# ab_v11_panel.net
KiCad netlist of a schematic drawn in EAGLE
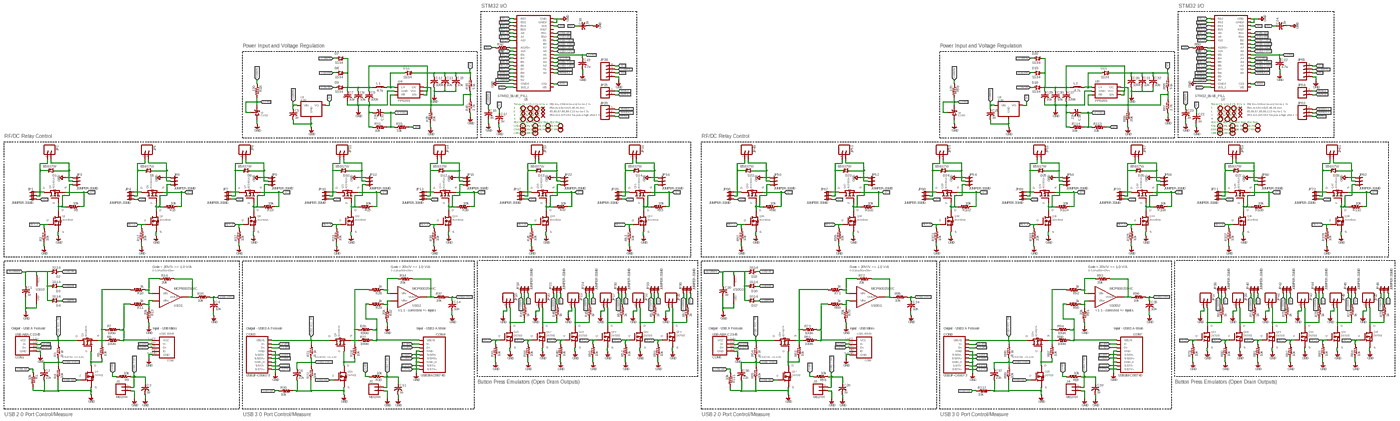
[diagram p0: schematic, sheet 1, overview]
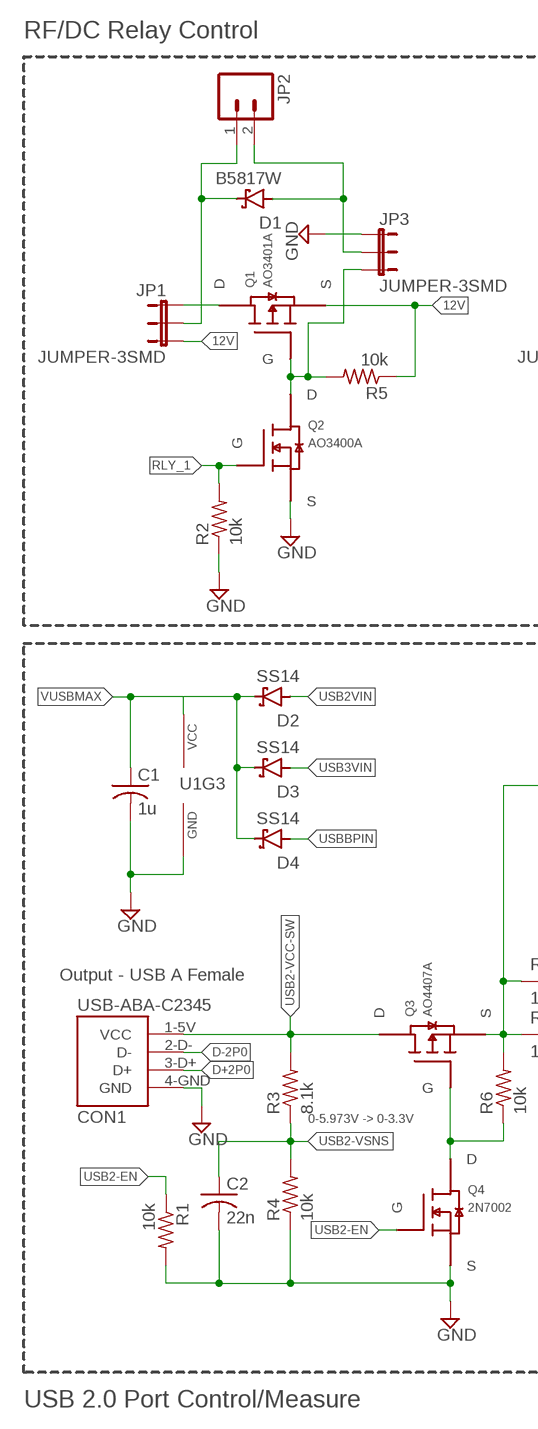
[diagram p1: schematic, sheet 1, part 1 of 4]
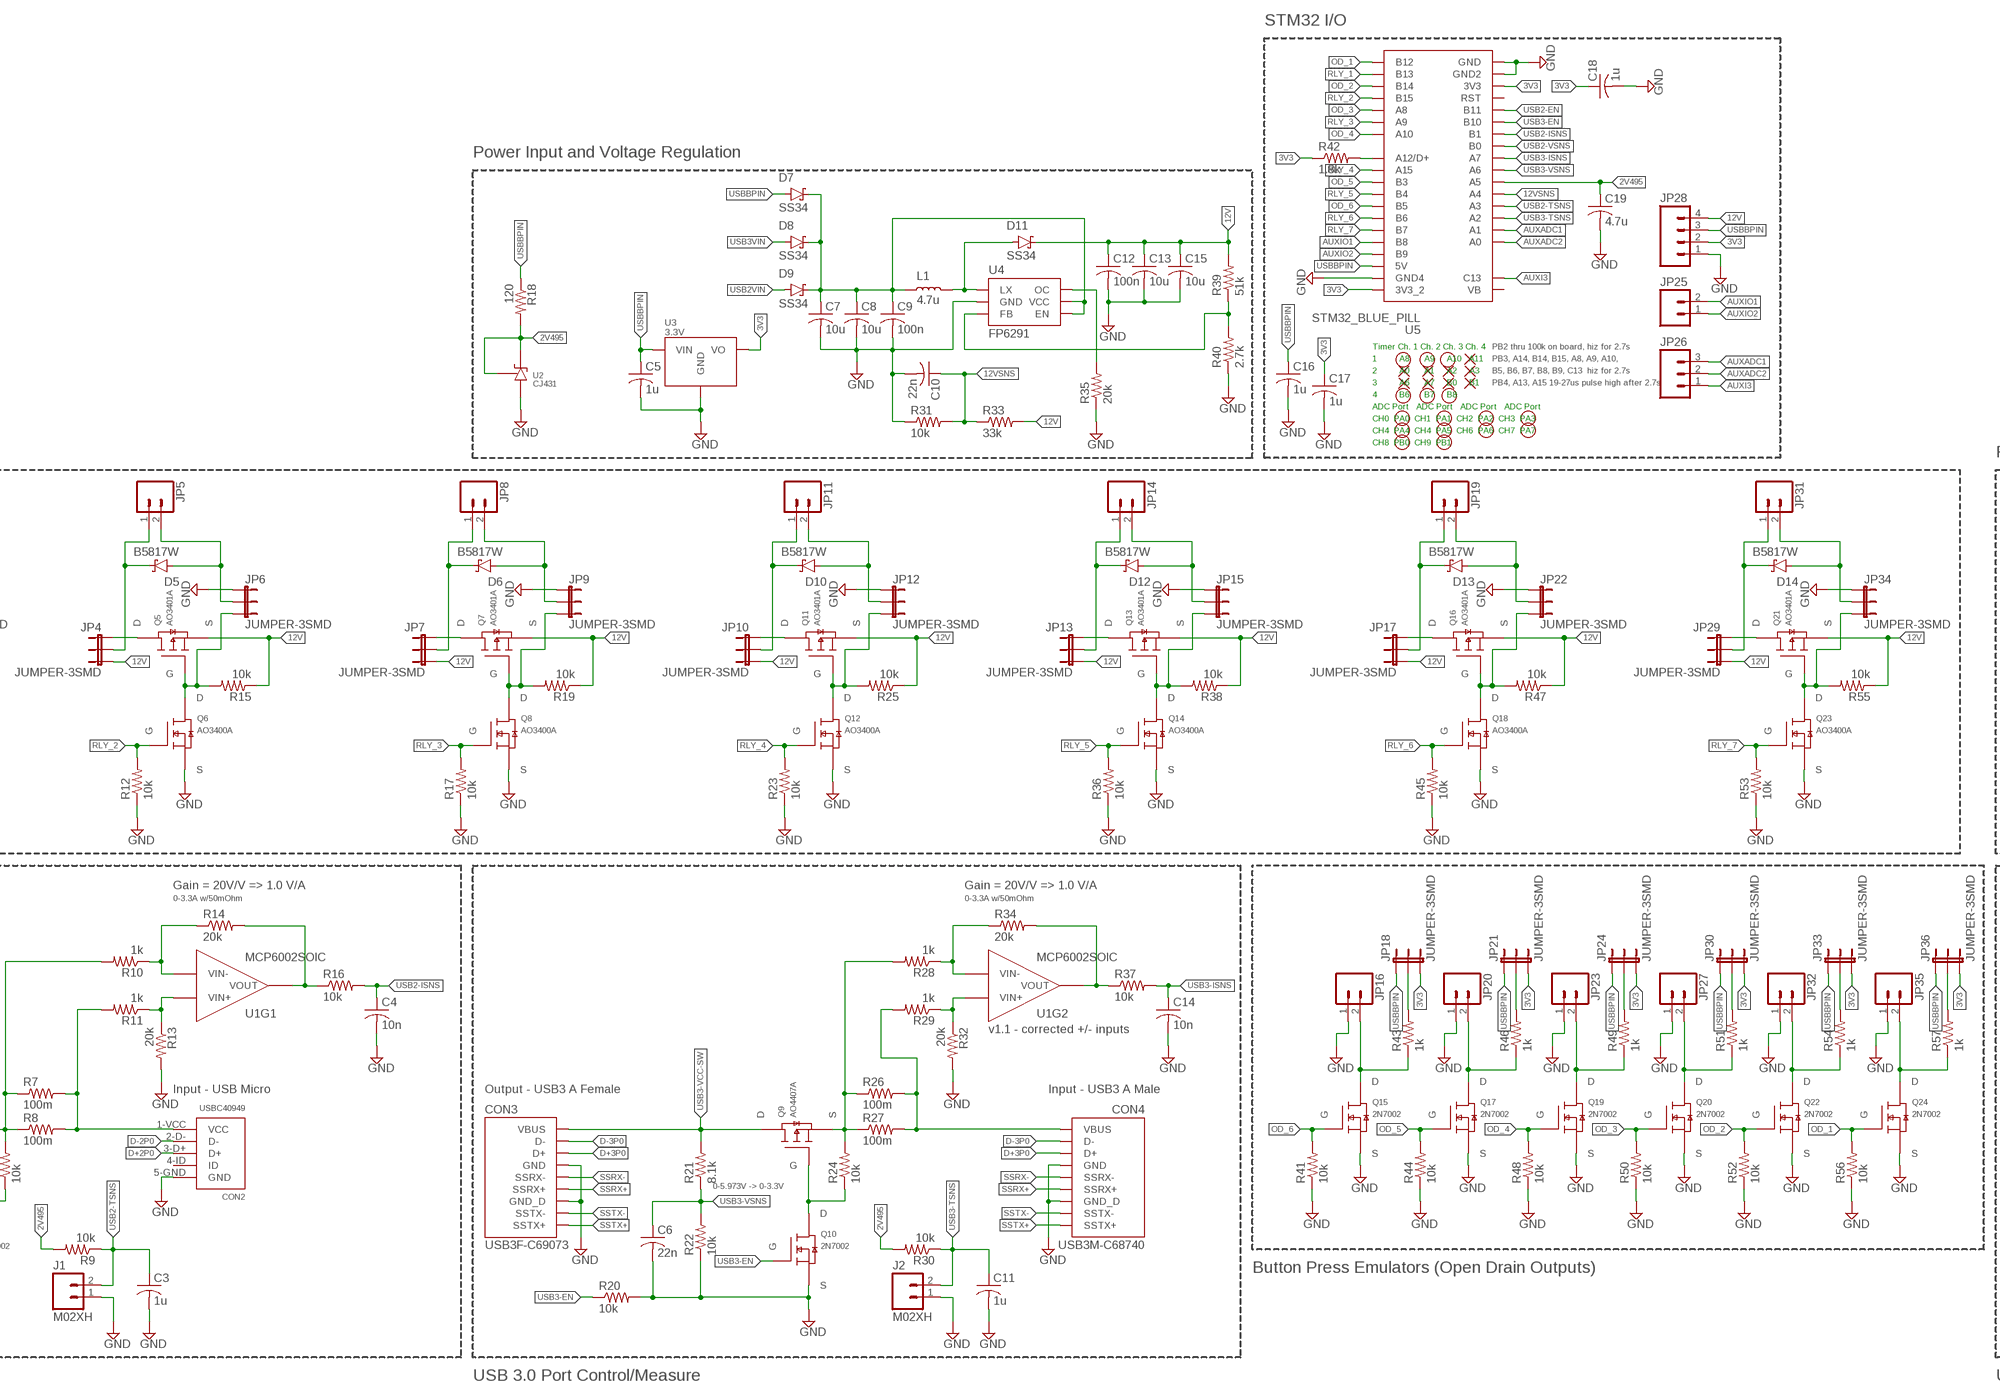
[diagram p2: schematic, sheet 1, part 2 of 4]
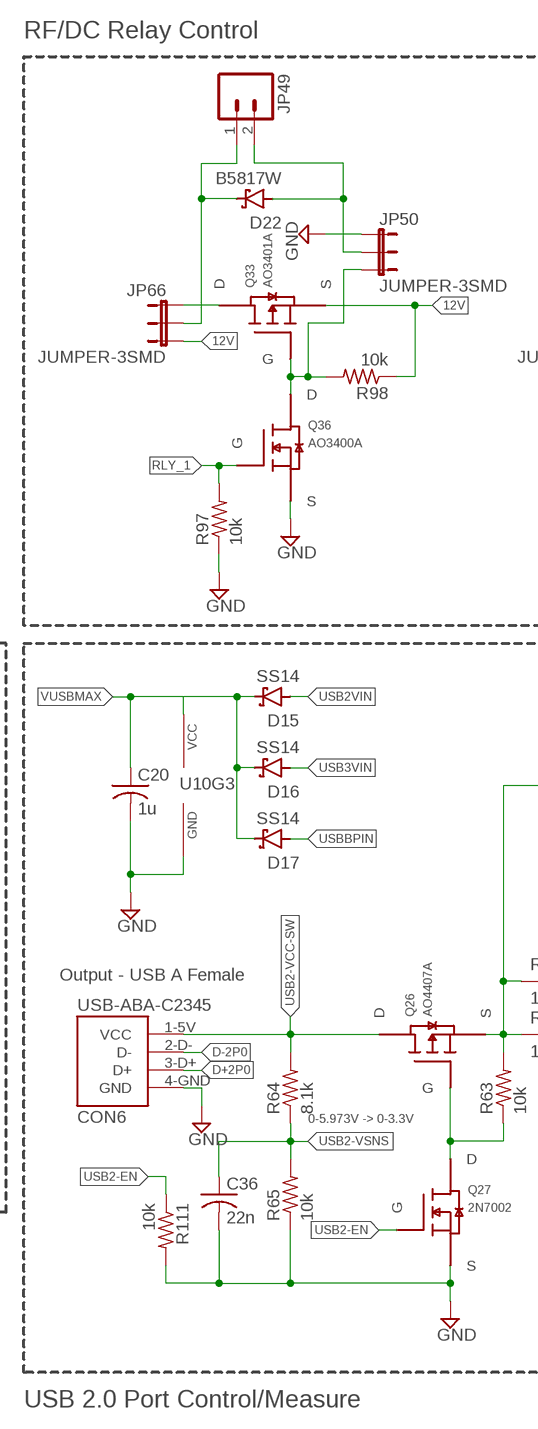
[diagram p3: schematic, sheet 1, part 3 of 4]
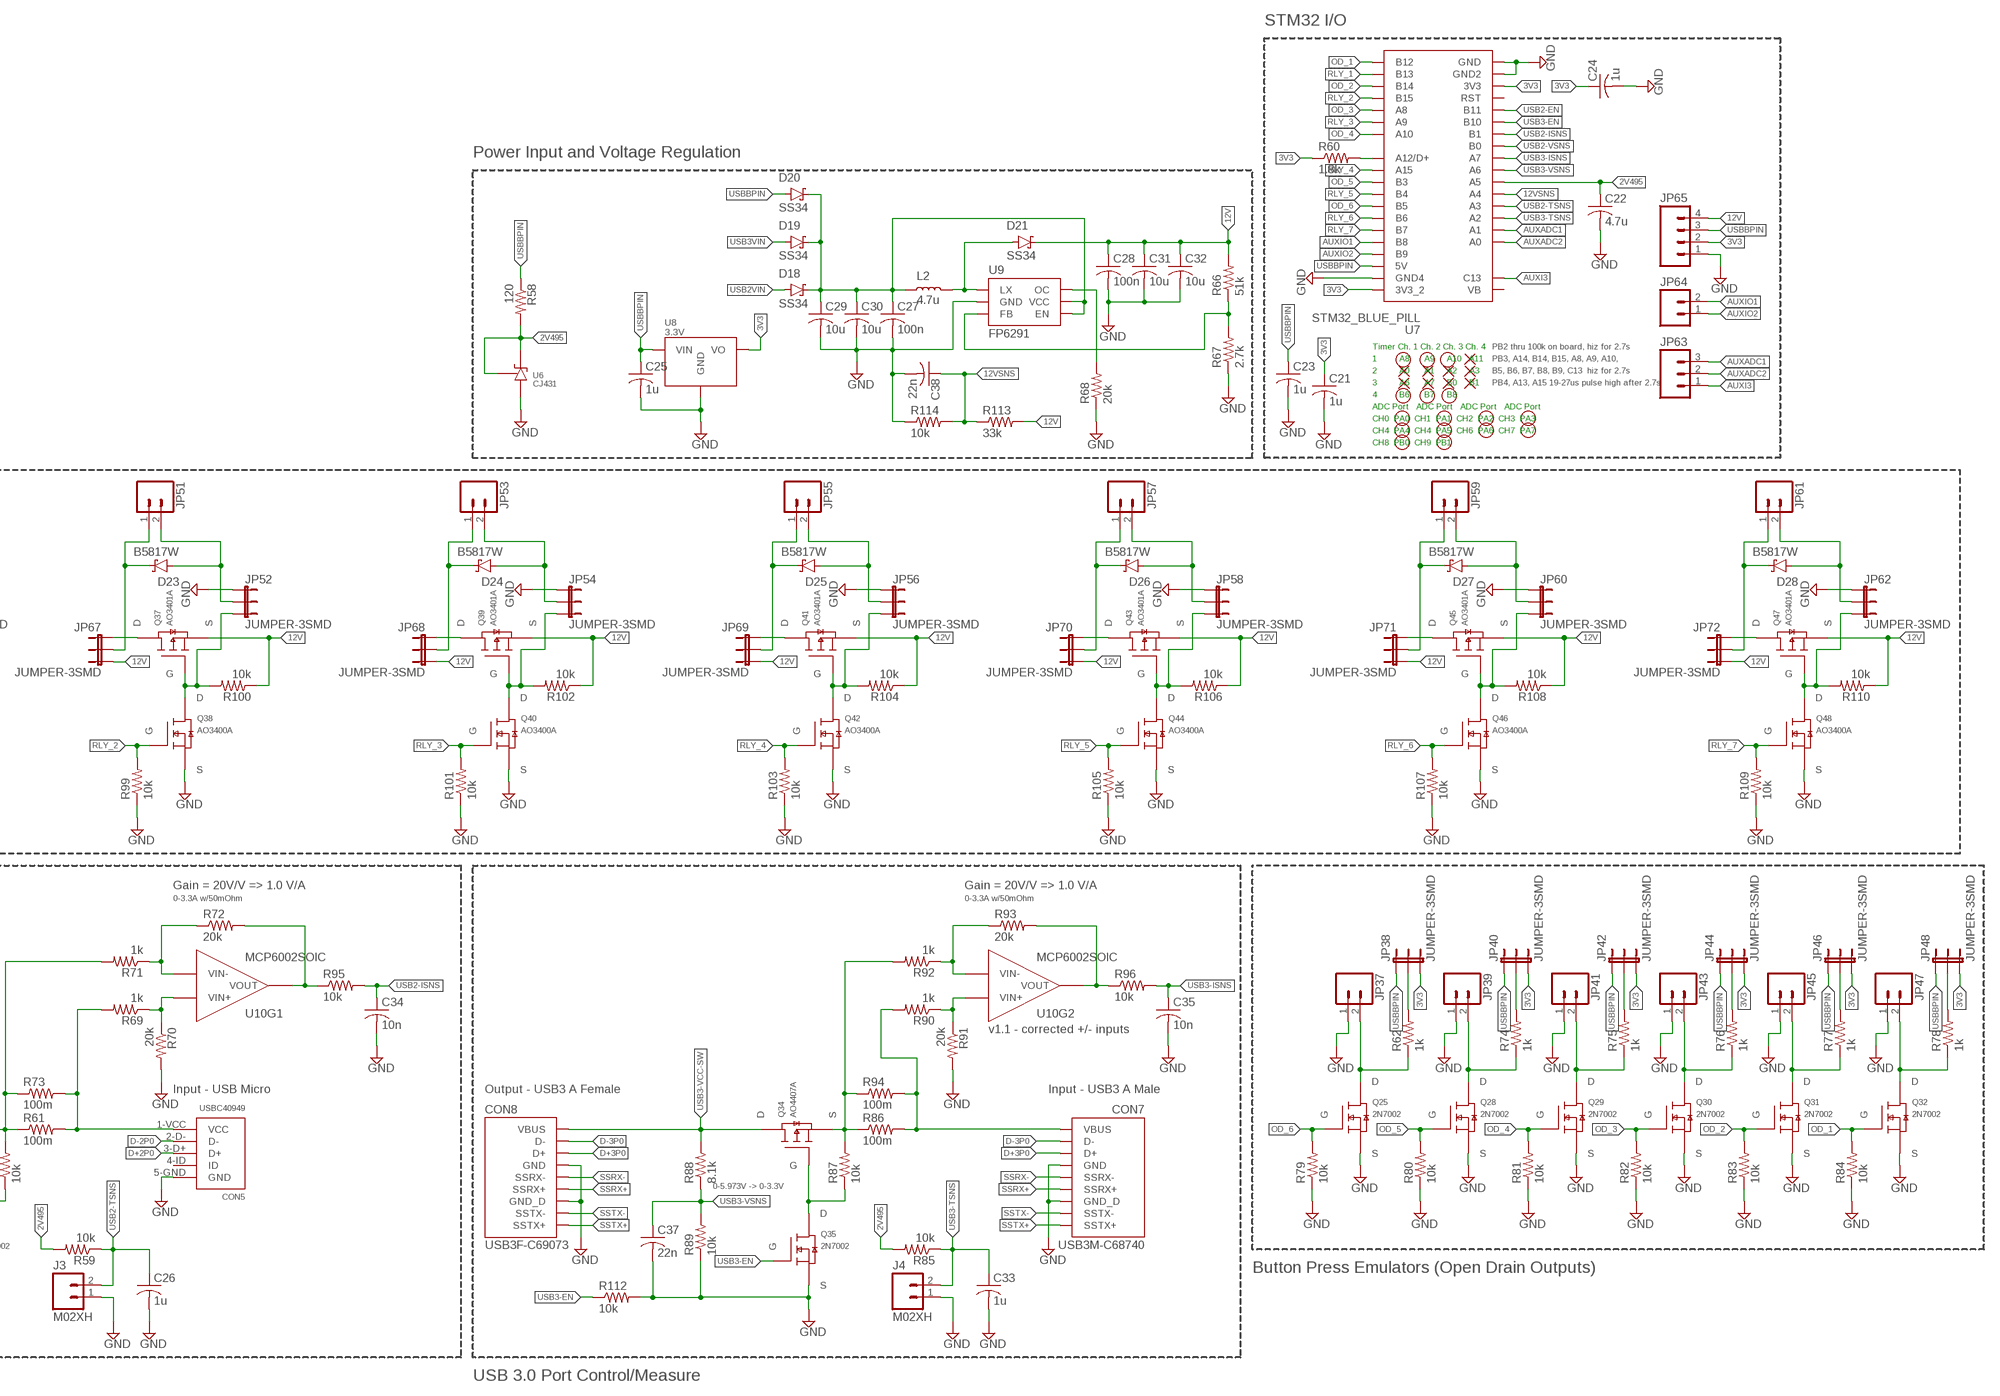
[diagram p4: schematic, sheet 1, part 4 of 4]

(export (version "E")
  (design (tool "Eeschema 10.0.6"))
  (components
    (comp (ref "C1")
      (value "1u")
      (footprint "eagle-import:C0402")
      (libsource (lib "eagle-import") (part "C-USC0402"))
    )
    (comp (ref "C2")
      (value "22n")
      (footprint "eagle-import:C0402")
      (libsource (lib "eagle-import") (part "C-USC0402"))
    )
    (comp (ref "C3")
      (value "1u")
      (footprint "eagle-import:C0402")
      (libsource (lib "eagle-import") (part "C-USC0402"))
    )
    (comp (ref "C4")
      (value "10n")
      (footprint "eagle-import:C0402")
      (libsource (lib "eagle-import") (part "C-USC0402"))
    )
    (comp (ref "C5")
      (value "1u")
      (footprint "eagle-import:C0402")
      (libsource (lib "eagle-import") (part "C-USC0402"))
    )
    (comp (ref "C6")
      (value "22n")
      (footprint "eagle-import:C0402")
      (libsource (lib "eagle-import") (part "C-USC0402"))
    )
    (comp (ref "C7")
      (value "10u")
      (footprint "eagle-import:C0603")
      (libsource (lib "eagle-import") (part "C-USC0603"))
    )
    (comp (ref "C8")
      (value "10u")
      (footprint "eagle-import:C0603")
      (libsource (lib "eagle-import") (part "C-USC0603"))
    )
    (comp (ref "C9")
      (value "100n")
      (footprint "eagle-import:C0402")
      (libsource (lib "eagle-import") (part "C-USC0402"))
    )
    (comp (ref "C10")
      (value "22n")
      (footprint "eagle-import:C0402")
      (libsource (lib "eagle-import") (part "C-USC0402"))
    )
    (comp (ref "C11")
      (value "1u")
      (footprint "eagle-import:C0402")
      (libsource (lib "eagle-import") (part "C-USC0402"))
    )
    (comp (ref "C12")
      (value "100n")
      (footprint "eagle-import:C0402")
      (libsource (lib "eagle-import") (part "C-USC0402"))
    )
    (comp (ref "C13")
      (value "10u")
      (footprint "eagle-import:C0805")
      (libsource (lib "eagle-import") (part "C-USC0805"))
    )
    (comp (ref "C14")
      (value "10n")
      (footprint "eagle-import:C0402")
      (libsource (lib "eagle-import") (part "C-USC0402"))
    )
    (comp (ref "C15")
      (value "10u")
      (footprint "eagle-import:C0805")
      (libsource (lib "eagle-import") (part "C-USC0805"))
    )
    (comp (ref "C16")
      (value "1u")
      (footprint "eagle-import:C0402")
      (libsource (lib "eagle-import") (part "C-USC0402"))
    )
    (comp (ref "C17")
      (value "1u")
      (footprint "eagle-import:C0402")
      (libsource (lib "eagle-import") (part "C-USC0402"))
    )
    (comp (ref "C18")
      (value "1u")
      (footprint "eagle-import:C0402")
      (libsource (lib "eagle-import") (part "C-USC0402"))
    )
    (comp (ref "C19")
      (value "4.7u")
      (footprint "eagle-import:C0402")
      (libsource (lib "eagle-import") (part "C-USC0402"))
    )
    (comp (ref "C20")
      (value "1u")
      (footprint "eagle-import:C0402")
      (libsource (lib "eagle-import") (part "C-USC0402"))
    )
    (comp (ref "C21")
      (value "1u")
      (footprint "eagle-import:C0402")
      (libsource (lib "eagle-import") (part "C-USC0402"))
    )
    (comp (ref "C22")
      (value "4.7u")
      (footprint "eagle-import:C0402")
      (libsource (lib "eagle-import") (part "C-USC0402"))
    )
    (comp (ref "C23")
      (value "1u")
      (footprint "eagle-import:C0402")
      (libsource (lib "eagle-import") (part "C-USC0402"))
    )
    (comp (ref "C24")
      (value "1u")
      (footprint "eagle-import:C0402")
      (libsource (lib "eagle-import") (part "C-USC0402"))
    )
    (comp (ref "C25")
      (value "1u")
      (footprint "eagle-import:C0402")
      (libsource (lib "eagle-import") (part "C-USC0402"))
    )
    (comp (ref "C26")
      (value "1u")
      (footprint "eagle-import:C0402")
      (libsource (lib "eagle-import") (part "C-USC0402"))
    )
    (comp (ref "C27")
      (value "100n")
      (footprint "eagle-import:C0402")
      (libsource (lib "eagle-import") (part "C-USC0402"))
    )
    (comp (ref "C28")
      (value "100n")
      (footprint "eagle-import:C0402")
      (libsource (lib "eagle-import") (part "C-USC0402"))
    )
    (comp (ref "C29")
      (value "10u")
      (footprint "eagle-import:C0603")
      (libsource (lib "eagle-import") (part "C-USC0603"))
    )
    (comp (ref "C30")
      (value "10u")
      (footprint "eagle-import:C0603")
      (libsource (lib "eagle-import") (part "C-USC0603"))
    )
    (comp (ref "C31")
      (value "10u")
      (footprint "eagle-import:C0805")
      (libsource (lib "eagle-import") (part "C-USC0805"))
    )
    (comp (ref "C32")
      (value "10u")
      (footprint "eagle-import:C0805")
      (libsource (lib "eagle-import") (part "C-USC0805"))
    )
    (comp (ref "C33")
      (value "1u")
      (footprint "eagle-import:C0402")
      (libsource (lib "eagle-import") (part "C-USC0402"))
    )
    (comp (ref "C34")
      (value "10n")
      (footprint "eagle-import:C0402")
      (libsource (lib "eagle-import") (part "C-USC0402"))
    )
    (comp (ref "C35")
      (value "10n")
      (footprint "eagle-import:C0402")
      (libsource (lib "eagle-import") (part "C-USC0402"))
    )
    (comp (ref "C36")
      (value "22n")
      (footprint "eagle-import:C0402")
      (libsource (lib "eagle-import") (part "C-USC0402"))
    )
    (comp (ref "C37")
      (value "22n")
      (footprint "eagle-import:C0402")
      (libsource (lib "eagle-import") (part "C-USC0402"))
    )
    (comp (ref "C38")
      (value "22n")
      (footprint "eagle-import:C0402")
      (libsource (lib "eagle-import") (part "C-USC0402"))
    )
    (comp (ref "CON1")
      (value "USB-ABA-C2345")
      (footprint "eagle-import:USB_A_C2345")
      (libsource (lib "eagle-import") (part "USB-ABA-C2345"))
    )
    (comp (ref "CON2")
      (value "USBC40949")
      (footprint "eagle-import:MICRO_USB-B_C40949")
      (libsource (lib "eagle-import") (part "USBC40949"))
    )
    (comp (ref "CON3")
      (value "USB3F-C69073")
      (footprint "eagle-import:USB3-F-C69073")
      (libsource (lib "eagle-import") (part "USB3F-C69073"))
    )
    (comp (ref "CON4")
      (value "USB3M-C68740")
      (footprint "eagle-import:USB3-M-C68740")
      (libsource (lib "eagle-import") (part "USB3M-C68740"))
    )
    (comp (ref "CON5")
      (value "USBC40949")
      (footprint "eagle-import:MICRO_USB-B_C40949")
      (libsource (lib "eagle-import") (part "USBC40949"))
    )
    (comp (ref "CON6")
      (value "USB-ABA-C2345")
      (footprint "eagle-import:USB_A_C2345")
      (libsource (lib "eagle-import") (part "USB-ABA-C2345"))
    )
    (comp (ref "CON7")
      (value "USB3M-C68740")
      (footprint "eagle-import:USB3-M-C68740")
      (libsource (lib "eagle-import") (part "USB3M-C68740"))
    )
    (comp (ref "CON8")
      (value "USB3F-C69073")
      (footprint "eagle-import:USB3-F-C69073")
      (libsource (lib "eagle-import") (part "USB3F-C69073"))
    )
    (comp (ref "D1")
      (value "B5817W")
      (footprint "eagle-import:SOD123W")
      (libsource (lib "eagle-import") (part "PMEG3020ER"))
    )
    (comp (ref "D2")
      (value "SS14")
      (footprint "eagle-import:SMA")
      (libsource (lib "eagle-import") (part "DIODE_SCHOTTKY_SMSSMA"))
    )
    (comp (ref "D3")
      (value "SS14")
      (footprint "eagle-import:SMA")
      (libsource (lib "eagle-import") (part "DIODE_SCHOTTKY_SMSSMA"))
    )
    (comp (ref "D4")
      (value "SS14")
      (footprint "eagle-import:SMA")
      (libsource (lib "eagle-import") (part "DIODE_SCHOTTKY_SMSSMA"))
    )
    (comp (ref "D5")
      (value "B5817W")
      (footprint "eagle-import:SOD123W")
      (libsource (lib "eagle-import") (part "PMEG3020ER"))
    )
    (comp (ref "D6")
      (value "B5817W")
      (footprint "eagle-import:SOD123W")
      (libsource (lib "eagle-import") (part "PMEG3020ER"))
    )
    (comp (ref "D7")
      (value "SS34")
      (footprint "eagle-import:SMA")
      (libsource (lib "eagle-import") (part "DIODE_SCHOTTKY_SMSSMA"))
    )
    (comp (ref "D8")
      (value "SS34")
      (footprint "eagle-import:SMA")
      (libsource (lib "eagle-import") (part "DIODE_SCHOTTKY_SMSSMA"))
    )
    (comp (ref "D9")
      (value "SS34")
      (footprint "eagle-import:SMA")
      (libsource (lib "eagle-import") (part "DIODE_SCHOTTKY_SMSSMA"))
    )
    (comp (ref "D10")
      (value "B5817W")
      (footprint "eagle-import:SOD123W")
      (libsource (lib "eagle-import") (part "PMEG3020ER"))
    )
    (comp (ref "D11")
      (value "SS34")
      (footprint "eagle-import:SMA")
      (libsource (lib "eagle-import") (part "DIODE_SCHOTTKY_SMSSMA"))
    )
    (comp (ref "D12")
      (value "B5817W")
      (footprint "eagle-import:SOD123W")
      (libsource (lib "eagle-import") (part "PMEG3020ER"))
    )
    (comp (ref "D13")
      (value "B5817W")
      (footprint "eagle-import:SOD123W")
      (libsource (lib "eagle-import") (part "PMEG3020ER"))
    )
    (comp (ref "D14")
      (value "B5817W")
      (footprint "eagle-import:SOD123W")
      (libsource (lib "eagle-import") (part "PMEG3020ER"))
    )
    (comp (ref "D15")
      (value "SS14")
      (footprint "eagle-import:SMA")
      (libsource (lib "eagle-import") (part "DIODE_SCHOTTKY_SMSSMA"))
    )
    (comp (ref "D16")
      (value "SS14")
      (footprint "eagle-import:SMA")
      (libsource (lib "eagle-import") (part "DIODE_SCHOTTKY_SMSSMA"))
    )
    (comp (ref "D17")
      (value "SS14")
      (footprint "eagle-import:SMA")
      (libsource (lib "eagle-import") (part "DIODE_SCHOTTKY_SMSSMA"))
    )
    (comp (ref "D18")
      (value "SS34")
      (footprint "eagle-import:SMA")
      (libsource (lib "eagle-import") (part "DIODE_SCHOTTKY_SMSSMA"))
    )
    (comp (ref "D19")
      (value "SS34")
      (footprint "eagle-import:SMA")
      (libsource (lib "eagle-import") (part "DIODE_SCHOTTKY_SMSSMA"))
    )
    (comp (ref "D20")
      (value "SS34")
      (footprint "eagle-import:SMA")
      (libsource (lib "eagle-import") (part "DIODE_SCHOTTKY_SMSSMA"))
    )
    (comp (ref "D21")
      (value "SS34")
      (footprint "eagle-import:SMA")
      (libsource (lib "eagle-import") (part "DIODE_SCHOTTKY_SMSSMA"))
    )
    (comp (ref "D22")
      (value "B5817W")
      (footprint "eagle-import:SOD123W")
      (libsource (lib "eagle-import") (part "PMEG3020ER"))
    )
    (comp (ref "D23")
      (value "B5817W")
      (footprint "eagle-import:SOD123W")
      (libsource (lib "eagle-import") (part "PMEG3020ER"))
    )
    (comp (ref "D24")
      (value "B5817W")
      (footprint "eagle-import:SOD123W")
      (libsource (lib "eagle-import") (part "PMEG3020ER"))
    )
    (comp (ref "D25")
      (value "B5817W")
      (footprint "eagle-import:SOD123W")
      (libsource (lib "eagle-import") (part "PMEG3020ER"))
    )
    (comp (ref "D26")
      (value "B5817W")
      (footprint "eagle-import:SOD123W")
      (libsource (lib "eagle-import") (part "PMEG3020ER"))
    )
    (comp (ref "D27")
      (value "B5817W")
      (footprint "eagle-import:SOD123W")
      (libsource (lib "eagle-import") (part "PMEG3020ER"))
    )
    (comp (ref "D28")
      (value "B5817W")
      (footprint "eagle-import:SOD123W")
      (libsource (lib "eagle-import") (part "PMEG3020ER"))
    )
    (comp (ref "J1")
      (value "M02XH")
      (footprint "eagle-import:B2B-XH-A")
      (libsource (lib "eagle-import") (part "M02XH"))
    )
    (comp (ref "J2")
      (value "M02XH")
      (footprint "eagle-import:B2B-XH-A")
      (libsource (lib "eagle-import") (part "M02XH"))
    )
    (comp (ref "J3")
      (value "M02XH")
      (footprint "eagle-import:B2B-XH-A")
      (libsource (lib "eagle-import") (part "M02XH"))
    )
    (comp (ref "J4")
      (value "M02XH")
      (footprint "eagle-import:B2B-XH-A")
      (libsource (lib "eagle-import") (part "M02XH"))
    )
    (comp (ref "JP1")
      (value "JUMPER-3SMD")
      (footprint "eagle-import:SJ_3")
      (libsource (lib "eagle-import") (part "JUMPER-3SMD"))
    )
    (comp (ref "JP2")
      (value "M02PTH")
      (footprint "eagle-import:1X02")
      (libsource (lib "eagle-import") (part "M02PTH"))
    )
    (comp (ref "JP3")
      (value "JUMPER-3SMD")
      (footprint "eagle-import:SJ_3")
      (libsource (lib "eagle-import") (part "JUMPER-3SMD"))
    )
    (comp (ref "JP4")
      (value "JUMPER-3SMD")
      (footprint "eagle-import:SJ_3")
      (libsource (lib "eagle-import") (part "JUMPER-3SMD"))
    )
    (comp (ref "JP5")
      (value "M02PTH")
      (footprint "eagle-import:1X02")
      (libsource (lib "eagle-import") (part "M02PTH"))
    )
    (comp (ref "JP6")
      (value "JUMPER-3SMD")
      (footprint "eagle-import:SJ_3")
      (libsource (lib "eagle-import") (part "JUMPER-3SMD"))
    )
    (comp (ref "JP7")
      (value "JUMPER-3SMD")
      (footprint "eagle-import:SJ_3")
      (libsource (lib "eagle-import") (part "JUMPER-3SMD"))
    )
    (comp (ref "JP8")
      (value "M02PTH")
      (footprint "eagle-import:1X02")
      (libsource (lib "eagle-import") (part "M02PTH"))
    )
    (comp (ref "JP9")
      (value "JUMPER-3SMD")
      (footprint "eagle-import:SJ_3")
      (libsource (lib "eagle-import") (part "JUMPER-3SMD"))
    )
    (comp (ref "JP10")
      (value "JUMPER-3SMD")
      (footprint "eagle-import:SJ_3")
      (libsource (lib "eagle-import") (part "JUMPER-3SMD"))
    )
    (comp (ref "JP11")
      (value "M02PTH")
      (footprint "eagle-import:1X02")
      (libsource (lib "eagle-import") (part "M02PTH"))
    )
    (comp (ref "JP12")
      (value "JUMPER-3SMD")
      (footprint "eagle-import:SJ_3")
      (libsource (lib "eagle-import") (part "JUMPER-3SMD"))
    )
    (comp (ref "JP13")
      (value "JUMPER-3SMD")
      (footprint "eagle-import:SJ_3")
      (libsource (lib "eagle-import") (part "JUMPER-3SMD"))
    )
    (comp (ref "JP14")
      (value "M02PTH")
      (footprint "eagle-import:1X02")
      (libsource (lib "eagle-import") (part "M02PTH"))
    )
    (comp (ref "JP15")
      (value "JUMPER-3SMD")
      (footprint "eagle-import:SJ_3")
      (libsource (lib "eagle-import") (part "JUMPER-3SMD"))
    )
    (comp (ref "JP16")
      (value "M02PTH")
      (footprint "eagle-import:1X02")
      (libsource (lib "eagle-import") (part "M02PTH"))
    )
    (comp (ref "JP17")
      (value "JUMPER-3SMD")
      (footprint "eagle-import:SJ_3")
      (libsource (lib "eagle-import") (part "JUMPER-3SMD"))
    )
    (comp (ref "JP18")
      (value "JUMPER-3SMD")
      (footprint "eagle-import:SJ_3")
      (libsource (lib "eagle-import") (part "JUMPER-3SMD"))
    )
    (comp (ref "JP19")
      (value "M02PTH")
      (footprint "eagle-import:1X02")
      (libsource (lib "eagle-import") (part "M02PTH"))
    )
    (comp (ref "JP20")
      (value "M02PTH")
      (footprint "eagle-import:1X02")
      (libsource (lib "eagle-import") (part "M02PTH"))
    )
    (comp (ref "JP21")
      (value "JUMPER-3SMD")
      (footprint "eagle-import:SJ_3")
      (libsource (lib "eagle-import") (part "JUMPER-3SMD"))
    )
    (comp (ref "JP22")
      (value "JUMPER-3SMD")
      (footprint "eagle-import:SJ_3")
      (libsource (lib "eagle-import") (part "JUMPER-3SMD"))
    )
    (comp (ref "JP23")
      (value "M02PTH")
      (footprint "eagle-import:1X02")
      (libsource (lib "eagle-import") (part "M02PTH"))
    )
    (comp (ref "JP24")
      (value "JUMPER-3SMD")
      (footprint "eagle-import:SJ_3")
      (libsource (lib "eagle-import") (part "JUMPER-3SMD"))
    )
    (comp (ref "JP25")
      (value "M02PTH")
      (footprint "eagle-import:1X02")
      (libsource (lib "eagle-import") (part "M02PTH"))
    )
    (comp (ref "JP26")
      (value "M03PTH")
      (footprint "eagle-import:1X03")
      (libsource (lib "eagle-import") (part "M03PTH"))
    )
    (comp (ref "JP27")
      (value "M02PTH")
      (footprint "eagle-import:1X02")
      (libsource (lib "eagle-import") (part "M02PTH"))
    )
    (comp (ref "JP28")
      (value "M04PTH")
      (footprint "eagle-import:1X04")
      (libsource (lib "eagle-import") (part "M04PTH"))
    )
    (comp (ref "JP29")
      (value "JUMPER-3SMD")
      (footprint "eagle-import:SJ_3")
      (libsource (lib "eagle-import") (part "JUMPER-3SMD"))
    )
    (comp (ref "JP30")
      (value "JUMPER-3SMD")
      (footprint "eagle-import:SJ_3")
      (libsource (lib "eagle-import") (part "JUMPER-3SMD"))
    )
    (comp (ref "JP31")
      (value "M02PTH")
      (footprint "eagle-import:1X02")
      (libsource (lib "eagle-import") (part "M02PTH"))
    )
    (comp (ref "JP32")
      (value "M02PTH")
      (footprint "eagle-import:1X02")
      (libsource (lib "eagle-import") (part "M02PTH"))
    )
    (comp (ref "JP33")
      (value "JUMPER-3SMD")
      (footprint "eagle-import:SJ_3")
      (libsource (lib "eagle-import") (part "JUMPER-3SMD"))
    )
    (comp (ref "JP34")
      (value "JUMPER-3SMD")
      (footprint "eagle-import:SJ_3")
      (libsource (lib "eagle-import") (part "JUMPER-3SMD"))
    )
    (comp (ref "JP35")
      (value "M02PTH")
      (footprint "eagle-import:1X02")
      (libsource (lib "eagle-import") (part "M02PTH"))
    )
    (comp (ref "JP36")
      (value "JUMPER-3SMD")
      (footprint "eagle-import:SJ_3")
      (libsource (lib "eagle-import") (part "JUMPER-3SMD"))
    )
    (comp (ref "JP37")
      (value "M02PTH")
      (footprint "eagle-import:1X02")
      (libsource (lib "eagle-import") (part "M02PTH"))
    )
    (comp (ref "JP38")
      (value "JUMPER-3SMD")
      (footprint "eagle-import:SJ_3")
      (libsource (lib "eagle-import") (part "JUMPER-3SMD"))
    )
    (comp (ref "JP39")
      (value "M02PTH")
      (footprint "eagle-import:1X02")
      (libsource (lib "eagle-import") (part "M02PTH"))
    )
    (comp (ref "JP40")
      (value "JUMPER-3SMD")
      (footprint "eagle-import:SJ_3")
      (libsource (lib "eagle-import") (part "JUMPER-3SMD"))
    )
    (comp (ref "JP41")
      (value "M02PTH")
      (footprint "eagle-import:1X02")
      (libsource (lib "eagle-import") (part "M02PTH"))
    )
    (comp (ref "JP42")
      (value "JUMPER-3SMD")
      (footprint "eagle-import:SJ_3")
      (libsource (lib "eagle-import") (part "JUMPER-3SMD"))
    )
    (comp (ref "JP43")
      (value "M02PTH")
      (footprint "eagle-import:1X02")
      (libsource (lib "eagle-import") (part "M02PTH"))
    )
    (comp (ref "JP44")
      (value "JUMPER-3SMD")
      (footprint "eagle-import:SJ_3")
      (libsource (lib "eagle-import") (part "JUMPER-3SMD"))
    )
    (comp (ref "JP45")
      (value "M02PTH")
      (footprint "eagle-import:1X02")
      (libsource (lib "eagle-import") (part "M02PTH"))
    )
    (comp (ref "JP46")
      (value "JUMPER-3SMD")
      (footprint "eagle-import:SJ_3")
      (libsource (lib "eagle-import") (part "JUMPER-3SMD"))
    )
    (comp (ref "JP47")
      (value "M02PTH")
      (footprint "eagle-import:1X02")
      (libsource (lib "eagle-import") (part "M02PTH"))
    )
    (comp (ref "JP48")
      (value "JUMPER-3SMD")
      (footprint "eagle-import:SJ_3")
      (libsource (lib "eagle-import") (part "JUMPER-3SMD"))
    )
    (comp (ref "JP49")
      (value "M02PTH")
      (footprint "eagle-import:1X02")
      (libsource (lib "eagle-import") (part "M02PTH"))
    )
    (comp (ref "JP50")
      (value "JUMPER-3SMD")
      (footprint "eagle-import:SJ_3")
      (libsource (lib "eagle-import") (part "JUMPER-3SMD"))
    )
    (comp (ref "JP51")
      (value "M02PTH")
      (footprint "eagle-import:1X02")
      (libsource (lib "eagle-import") (part "M02PTH"))
    )
    (comp (ref "JP52")
      (value "JUMPER-3SMD")
      (footprint "eagle-import:SJ_3")
      (libsource (lib "eagle-import") (part "JUMPER-3SMD"))
    )
    (comp (ref "JP53")
      (value "M02PTH")
      (footprint "eagle-import:1X02")
      (libsource (lib "eagle-import") (part "M02PTH"))
    )
    (comp (ref "JP54")
      (value "JUMPER-3SMD")
      (footprint "eagle-import:SJ_3")
      (libsource (lib "eagle-import") (part "JUMPER-3SMD"))
    )
    (comp (ref "JP55")
      (value "M02PTH")
      (footprint "eagle-import:1X02")
      (libsource (lib "eagle-import") (part "M02PTH"))
    )
    (comp (ref "JP56")
      (value "JUMPER-3SMD")
      (footprint "eagle-import:SJ_3")
      (libsource (lib "eagle-import") (part "JUMPER-3SMD"))
    )
    (comp (ref "JP57")
      (value "M02PTH")
      (footprint "eagle-import:1X02")
      (libsource (lib "eagle-import") (part "M02PTH"))
    )
    (comp (ref "JP58")
      (value "JUMPER-3SMD")
      (footprint "eagle-import:SJ_3")
      (libsource (lib "eagle-import") (part "JUMPER-3SMD"))
    )
    (comp (ref "JP59")
      (value "M02PTH")
      (footprint "eagle-import:1X02")
      (libsource (lib "eagle-import") (part "M02PTH"))
    )
    (comp (ref "JP60")
      (value "JUMPER-3SMD")
      (footprint "eagle-import:SJ_3")
      (libsource (lib "eagle-import") (part "JUMPER-3SMD"))
    )
    (comp (ref "JP61")
      (value "M02PTH")
      (footprint "eagle-import:1X02")
      (libsource (lib "eagle-import") (part "M02PTH"))
    )
    (comp (ref "JP62")
      (value "JUMPER-3SMD")
      (footprint "eagle-import:SJ_3")
      (libsource (lib "eagle-import") (part "JUMPER-3SMD"))
    )
    (comp (ref "JP63")
      (value "M03PTH")
      (footprint "eagle-import:1X03")
      (libsource (lib "eagle-import") (part "M03PTH"))
    )
    (comp (ref "JP64")
      (value "M02PTH")
      (footprint "eagle-import:1X02")
      (libsource (lib "eagle-import") (part "M02PTH"))
    )
    (comp (ref "JP65")
      (value "M04PTH")
      (footprint "eagle-import:1X04")
      (libsource (lib "eagle-import") (part "M04PTH"))
    )
    (comp (ref "JP66")
      (value "JUMPER-3SMD")
      (footprint "eagle-import:SJ_3")
      (libsource (lib "eagle-import") (part "JUMPER-3SMD"))
    )
    (comp (ref "JP67")
      (value "JUMPER-3SMD")
      (footprint "eagle-import:SJ_3")
      (libsource (lib "eagle-import") (part "JUMPER-3SMD"))
    )
    (comp (ref "JP68")
      (value "JUMPER-3SMD")
      (footprint "eagle-import:SJ_3")
      (libsource (lib "eagle-import") (part "JUMPER-3SMD"))
    )
    (comp (ref "JP69")
      (value "JUMPER-3SMD")
      (footprint "eagle-import:SJ_3")
      (libsource (lib "eagle-import") (part "JUMPER-3SMD"))
    )
    (comp (ref "JP70")
      (value "JUMPER-3SMD")
      (footprint "eagle-import:SJ_3")
      (libsource (lib "eagle-import") (part "JUMPER-3SMD"))
    )
    (comp (ref "JP71")
      (value "JUMPER-3SMD")
      (footprint "eagle-import:SJ_3")
      (libsource (lib "eagle-import") (part "JUMPER-3SMD"))
    )
    (comp (ref "JP72")
      (value "JUMPER-3SMD")
      (footprint "eagle-import:SJ_3")
      (libsource (lib "eagle-import") (part "JUMPER-3SMD"))
    )
    (comp (ref "L1")
      (value "4.7u")
      (footprint "eagle-import:INDUCTOR_6X6")
      (libsource (lib "eagle-import") (part "INDUCTOR6X6"))
    )
    (comp (ref "L2")
      (value "4.7u")
      (footprint "eagle-import:INDUCTOR_6X6")
      (libsource (lib "eagle-import") (part "INDUCTOR6X6"))
    )
    (comp (ref "Q1")
      (value "AO3401A")
      (footprint "eagle-import:SOT23")
      (libsource (lib "eagle-import") (part "AO3401A"))
    )
    (comp (ref "Q2")
      (value "AO3400A")
      (footprint "eagle-import:SOT23")
      (libsource (lib "eagle-import") (part "2N7002P"))
    )
    (comp (ref "Q3")
      (value "AO4407A")
      (footprint "eagle-import:8-SOIC")
      (libsource (lib "eagle-import") (part "P-MOSFET-SOIC8"))
    )
    (comp (ref "Q4")
      (value "2N7002")
      (footprint "eagle-import:SOT23")
      (libsource (lib "eagle-import") (part "2N7002P"))
    )
    (comp (ref "Q5")
      (value "AO3401A")
      (footprint "eagle-import:SOT23")
      (libsource (lib "eagle-import") (part "AO3401A"))
    )
    (comp (ref "Q6")
      (value "AO3400A")
      (footprint "eagle-import:SOT23")
      (libsource (lib "eagle-import") (part "2N7002P"))
    )
    (comp (ref "Q7")
      (value "AO3401A")
      (footprint "eagle-import:SOT23")
      (libsource (lib "eagle-import") (part "AO3401A"))
    )
    (comp (ref "Q8")
      (value "AO3400A")
      (footprint "eagle-import:SOT23")
      (libsource (lib "eagle-import") (part "2N7002P"))
    )
    (comp (ref "Q9")
      (value "AO4407A")
      (footprint "eagle-import:8-SOIC")
      (libsource (lib "eagle-import") (part "P-MOSFET-SOIC8"))
    )
    (comp (ref "Q10")
      (value "2N7002")
      (footprint "eagle-import:SOT23")
      (libsource (lib "eagle-import") (part "2N7002P"))
    )
    (comp (ref "Q11")
      (value "AO3401A")
      (footprint "eagle-import:SOT23")
      (libsource (lib "eagle-import") (part "AO3401A"))
    )
    (comp (ref "Q12")
      (value "AO3400A")
      (footprint "eagle-import:SOT23")
      (libsource (lib "eagle-import") (part "2N7002P"))
    )
    (comp (ref "Q13")
      (value "AO3401A")
      (footprint "eagle-import:SOT23")
      (libsource (lib "eagle-import") (part "AO3401A"))
    )
    (comp (ref "Q14")
      (value "AO3400A")
      (footprint "eagle-import:SOT23")
      (libsource (lib "eagle-import") (part "2N7002P"))
    )
    (comp (ref "Q15")
      (value "2N7002")
      (footprint "eagle-import:SOT23")
      (libsource (lib "eagle-import") (part "2N7002P"))
    )
    (comp (ref "Q16")
      (value "AO3401A")
      (footprint "eagle-import:SOT23")
      (libsource (lib "eagle-import") (part "AO3401A"))
    )
    (comp (ref "Q17")
      (value "2N7002")
      (footprint "eagle-import:SOT23")
      (libsource (lib "eagle-import") (part "2N7002P"))
    )
    (comp (ref "Q18")
      (value "AO3400A")
      (footprint "eagle-import:SOT23")
      (libsource (lib "eagle-import") (part "2N7002P"))
    )
    (comp (ref "Q19")
      (value "2N7002")
      (footprint "eagle-import:SOT23")
      (libsource (lib "eagle-import") (part "2N7002P"))
    )
    (comp (ref "Q20")
      (value "2N7002")
      (footprint "eagle-import:SOT23")
      (libsource (lib "eagle-import") (part "2N7002P"))
    )
    (comp (ref "Q21")
      (value "AO3401A")
      (footprint "eagle-import:SOT23")
      (libsource (lib "eagle-import") (part "AO3401A"))
    )
    (comp (ref "Q22")
      (value "2N7002")
      (footprint "eagle-import:SOT23")
      (libsource (lib "eagle-import") (part "2N7002P"))
    )
    (comp (ref "Q23")
      (value "AO3400A")
      (footprint "eagle-import:SOT23")
      (libsource (lib "eagle-import") (part "2N7002P"))
    )
    (comp (ref "Q24")
      (value "2N7002")
      (footprint "eagle-import:SOT23")
      (libsource (lib "eagle-import") (part "2N7002P"))
    )
    (comp (ref "Q25")
      (value "2N7002")
      (footprint "eagle-import:SOT23")
      (libsource (lib "eagle-import") (part "2N7002P"))
    )
    (comp (ref "Q26")
      (value "AO4407A")
      (footprint "eagle-import:8-SOIC")
      (libsource (lib "eagle-import") (part "P-MOSFET-SOIC8"))
    )
    (comp (ref "Q27")
      (value "2N7002")
      (footprint "eagle-import:SOT23")
      (libsource (lib "eagle-import") (part "2N7002P"))
    )
    (comp (ref "Q28")
      (value "2N7002")
      (footprint "eagle-import:SOT23")
      (libsource (lib "eagle-import") (part "2N7002P"))
    )
    (comp (ref "Q29")
      (value "2N7002")
      (footprint "eagle-import:SOT23")
      (libsource (lib "eagle-import") (part "2N7002P"))
    )
    (comp (ref "Q30")
      (value "2N7002")
      (footprint "eagle-import:SOT23")
      (libsource (lib "eagle-import") (part "2N7002P"))
    )
    (comp (ref "Q31")
      (value "2N7002")
      (footprint "eagle-import:SOT23")
      (libsource (lib "eagle-import") (part "2N7002P"))
    )
    (comp (ref "Q32")
      (value "2N7002")
      (footprint "eagle-import:SOT23")
      (libsource (lib "eagle-import") (part "2N7002P"))
    )
    (comp (ref "Q33")
      (value "AO3401A")
      (footprint "eagle-import:SOT23")
      (libsource (lib "eagle-import") (part "AO3401A"))
    )
    (comp (ref "Q34")
      (value "AO4407A")
      (footprint "eagle-import:8-SOIC")
      (libsource (lib "eagle-import") (part "P-MOSFET-SOIC8"))
    )
    (comp (ref "Q35")
      (value "2N7002")
      (footprint "eagle-import:SOT23")
      (libsource (lib "eagle-import") (part "2N7002P"))
    )
    (comp (ref "Q36")
      (value "AO3400A")
      (footprint "eagle-import:SOT23")
      (libsource (lib "eagle-import") (part "2N7002P"))
    )
    (comp (ref "Q37")
      (value "AO3401A")
      (footprint "eagle-import:SOT23")
      (libsource (lib "eagle-import") (part "AO3401A"))
    )
    (comp (ref "Q38")
      (value "AO3400A")
      (footprint "eagle-import:SOT23")
      (libsource (lib "eagle-import") (part "2N7002P"))
    )
    (comp (ref "Q39")
      (value "AO3401A")
      (footprint "eagle-import:SOT23")
      (libsource (lib "eagle-import") (part "AO3401A"))
    )
    (comp (ref "Q40")
      (value "AO3400A")
      (footprint "eagle-import:SOT23")
      (libsource (lib "eagle-import") (part "2N7002P"))
    )
    (comp (ref "Q41")
      (value "AO3401A")
      (footprint "eagle-import:SOT23")
      (libsource (lib "eagle-import") (part "AO3401A"))
    )
    (comp (ref "Q42")
      (value "AO3400A")
      (footprint "eagle-import:SOT23")
      (libsource (lib "eagle-import") (part "2N7002P"))
    )
    (comp (ref "Q43")
      (value "AO3401A")
      (footprint "eagle-import:SOT23")
      (libsource (lib "eagle-import") (part "AO3401A"))
    )
    (comp (ref "Q44")
      (value "AO3400A")
      (footprint "eagle-import:SOT23")
      (libsource (lib "eagle-import") (part "2N7002P"))
    )
    (comp (ref "Q45")
      (value "AO3401A")
      (footprint "eagle-import:SOT23")
      (libsource (lib "eagle-import") (part "AO3401A"))
    )
    (comp (ref "Q46")
      (value "AO3400A")
      (footprint "eagle-import:SOT23")
      (libsource (lib "eagle-import") (part "2N7002P"))
    )
    (comp (ref "Q47")
      (value "AO3401A")
      (footprint "eagle-import:SOT23")
      (libsource (lib "eagle-import") (part "AO3401A"))
    )
    (comp (ref "Q48")
      (value "AO3400A")
      (footprint "eagle-import:SOT23")
      (libsource (lib "eagle-import") (part "2N7002P"))
    )
    (comp (ref "R1")
      (value "10k")
      (footprint "eagle-import:R0402")
      (libsource (lib "eagle-import") (part "R-US_R0402"))
    )
    (comp (ref "R2")
      (value "10k")
      (footprint "eagle-import:R0402")
      (libsource (lib "eagle-import") (part "R-US_R0402"))
    )
    (comp (ref "R3")
      (value "8.1k")
      (footprint "eagle-import:R0402")
      (libsource (lib "eagle-import") (part "R-US_R0402"))
    )
    (comp (ref "R4")
      (value "10k")
      (footprint "eagle-import:R0402")
      (libsource (lib "eagle-import") (part "R-US_R0402"))
    )
    (comp (ref "R5")
      (value "10k")
      (footprint "eagle-import:R0402")
      (libsource (lib "eagle-import") (part "R-US_R0402"))
    )
    (comp (ref "R6")
      (value "10k")
      (footprint "eagle-import:R0402")
      (libsource (lib "eagle-import") (part "R-US_R0402"))
    )
    (comp (ref "R7")
      (value "100m")
      (footprint "eagle-import:R1206")
      (libsource (lib "eagle-import") (part "R-US_R1206"))
    )
    (comp (ref "R8")
      (value "100m")
      (footprint "eagle-import:R1206")
      (libsource (lib "eagle-import") (part "R-US_R1206"))
    )
    (comp (ref "R9")
      (value "10k")
      (footprint "eagle-import:R0402")
      (libsource (lib "eagle-import") (part "R-US_R0402"))
    )
    (comp (ref "R10")
      (value "1k")
      (footprint "eagle-import:R0402")
      (libsource (lib "eagle-import") (part "R-US_R0402"))
    )
    (comp (ref "R11")
      (value "1k")
      (footprint "eagle-import:R0402")
      (libsource (lib "eagle-import") (part "R-US_R0402"))
    )
    (comp (ref "R12")
      (value "10k")
      (footprint "eagle-import:R0402")
      (libsource (lib "eagle-import") (part "R-US_R0402"))
    )
    (comp (ref "R13")
      (value "20k")
      (footprint "eagle-import:R0402")
      (libsource (lib "eagle-import") (part "R-US_R0402"))
    )
    (comp (ref "R14")
      (value "20k")
      (footprint "eagle-import:R0402")
      (libsource (lib "eagle-import") (part "R-US_R0402"))
    )
    (comp (ref "R15")
      (value "10k")
      (footprint "eagle-import:R0402")
      (libsource (lib "eagle-import") (part "R-US_R0402"))
    )
    (comp (ref "R16")
      (value "10k")
      (footprint "eagle-import:R0402")
      (libsource (lib "eagle-import") (part "R-US_R0402"))
    )
    (comp (ref "R17")
      (value "10k")
      (footprint "eagle-import:R0402")
      (libsource (lib "eagle-import") (part "R-US_R0402"))
    )
    (comp (ref "R18")
      (value "120")
      (footprint "eagle-import:R0402")
      (libsource (lib "eagle-import") (part "R-US_R0402"))
    )
    (comp (ref "R19")
      (value "10k")
      (footprint "eagle-import:R0402")
      (libsource (lib "eagle-import") (part "R-US_R0402"))
    )
    (comp (ref "R20")
      (value "10k")
      (footprint "eagle-import:R0402")
      (libsource (lib "eagle-import") (part "R-US_R0402"))
    )
    (comp (ref "R21")
      (value "8.1k")
      (footprint "eagle-import:R0402")
      (libsource (lib "eagle-import") (part "R-US_R0402"))
    )
    (comp (ref "R22")
      (value "10k")
      (footprint "eagle-import:R0402")
      (libsource (lib "eagle-import") (part "R-US_R0402"))
    )
    (comp (ref "R23")
      (value "10k")
      (footprint "eagle-import:R0402")
      (libsource (lib "eagle-import") (part "R-US_R0402"))
    )
    (comp (ref "R24")
      (value "10k")
      (footprint "eagle-import:R0402")
      (libsource (lib "eagle-import") (part "R-US_R0402"))
    )
    (comp (ref "R25")
      (value "10k")
      (footprint "eagle-import:R0402")
      (libsource (lib "eagle-import") (part "R-US_R0402"))
    )
    (comp (ref "R26")
      (value "100m")
      (footprint "eagle-import:R1206")
      (libsource (lib "eagle-import") (part "R-US_R1206"))
    )
    (comp (ref "R27")
      (value "100m")
      (footprint "eagle-import:R1206")
      (libsource (lib "eagle-import") (part "R-US_R1206"))
    )
    (comp (ref "R28")
      (value "1k")
      (footprint "eagle-import:R0402")
      (libsource (lib "eagle-import") (part "R-US_R0402"))
    )
    (comp (ref "R29")
      (value "1k")
      (footprint "eagle-import:R0402")
      (libsource (lib "eagle-import") (part "R-US_R0402"))
    )
    (comp (ref "R30")
      (value "10k")
      (footprint "eagle-import:R0402")
      (libsource (lib "eagle-import") (part "R-US_R0402"))
    )
    (comp (ref "R31")
      (value "10k")
      (footprint "eagle-import:R0402")
      (libsource (lib "eagle-import") (part "R-US_R0402"))
    )
    (comp (ref "R32")
      (value "20k")
      (footprint "eagle-import:R0402")
      (libsource (lib "eagle-import") (part "R-US_R0402"))
    )
    (comp (ref "R33")
      (value "33k")
      (footprint "eagle-import:R0402")
      (libsource (lib "eagle-import") (part "R-US_R0402"))
    )
    (comp (ref "R34")
      (value "20k")
      (footprint "eagle-import:R0402")
      (libsource (lib "eagle-import") (part "R-US_R0402"))
    )
    (comp (ref "R35")
      (value "20k")
      (footprint "eagle-import:R0402")
      (libsource (lib "eagle-import") (part "R-US_R0402"))
    )
    (comp (ref "R36")
      (value "10k")
      (footprint "eagle-import:R0402")
      (libsource (lib "eagle-import") (part "R-US_R0402"))
    )
    (comp (ref "R37")
      (value "10k")
      (footprint "eagle-import:R0402")
      (libsource (lib "eagle-import") (part "R-US_R0402"))
    )
    (comp (ref "R38")
      (value "10k")
      (footprint "eagle-import:R0402")
      (libsource (lib "eagle-import") (part "R-US_R0402"))
    )
    (comp (ref "R39")
      (value "51k")
      (footprint "eagle-import:R0402")
      (libsource (lib "eagle-import") (part "R-US_R0402"))
    )
    (comp (ref "R40")
      (value "2.7k")
      (footprint "eagle-import:R0402")
      (libsource (lib "eagle-import") (part "R-US_R0402"))
    )
    (comp (ref "R41")
      (value "10k")
      (footprint "eagle-import:R0402")
      (libsource (lib "eagle-import") (part "R-US_R0402"))
    )
    (comp (ref "R42")
      (value "1.8k")
      (footprint "eagle-import:R0402")
      (libsource (lib "eagle-import") (part "R-US_R0402"))
    )
    (comp (ref "R43")
      (value "1k")
      (footprint "eagle-import:R0402")
      (libsource (lib "eagle-import") (part "R-US_R0402"))
    )
    (comp (ref "R44")
      (value "10k")
      (footprint "eagle-import:R0402")
      (libsource (lib "eagle-import") (part "R-US_R0402"))
    )
    (comp (ref "R45")
      (value "10k")
      (footprint "eagle-import:R0402")
      (libsource (lib "eagle-import") (part "R-US_R0402"))
    )
    (comp (ref "R46")
      (value "1k")
      (footprint "eagle-import:R0402")
      (libsource (lib "eagle-import") (part "R-US_R0402"))
    )
    (comp (ref "R47")
      (value "10k")
      (footprint "eagle-import:R0402")
      (libsource (lib "eagle-import") (part "R-US_R0402"))
    )
    (comp (ref "R48")
      (value "10k")
      (footprint "eagle-import:R0402")
      (libsource (lib "eagle-import") (part "R-US_R0402"))
    )
    (comp (ref "R49")
      (value "1k")
      (footprint "eagle-import:R0402")
      (libsource (lib "eagle-import") (part "R-US_R0402"))
    )
    (comp (ref "R50")
      (value "10k")
      (footprint "eagle-import:R0402")
      (libsource (lib "eagle-import") (part "R-US_R0402"))
    )
    (comp (ref "R51")
      (value "1k")
      (footprint "eagle-import:R0402")
      (libsource (lib "eagle-import") (part "R-US_R0402"))
    )
    (comp (ref "R52")
      (value "10k")
      (footprint "eagle-import:R0402")
      (libsource (lib "eagle-import") (part "R-US_R0402"))
    )
    (comp (ref "R53")
      (value "10k")
      (footprint "eagle-import:R0402")
      (libsource (lib "eagle-import") (part "R-US_R0402"))
    )
    (comp (ref "R54")
      (value "1k")
      (footprint "eagle-import:R0402")
      (libsource (lib "eagle-import") (part "R-US_R0402"))
    )
    (comp (ref "R55")
      (value "10k")
      (footprint "eagle-import:R0402")
      (libsource (lib "eagle-import") (part "R-US_R0402"))
    )
    (comp (ref "R56")
      (value "10k")
      (footprint "eagle-import:R0402")
      (libsource (lib "eagle-import") (part "R-US_R0402"))
    )
    (comp (ref "R57")
      (value "1k")
      (footprint "eagle-import:R0402")
      (libsource (lib "eagle-import") (part "R-US_R0402"))
    )
    (comp (ref "R58")
      (value "120")
      (footprint "eagle-import:R0402")
      (libsource (lib "eagle-import") (part "R-US_R0402"))
    )
    (comp (ref "R59")
      (value "10k")
      (footprint "eagle-import:R0402")
      (libsource (lib "eagle-import") (part "R-US_R0402"))
    )
    (comp (ref "R60")
      (value "1.8k")
      (footprint "eagle-import:R0402")
      (libsource (lib "eagle-import") (part "R-US_R0402"))
    )
    (comp (ref "R61")
      (value "100m")
      (footprint "eagle-import:R1206")
      (libsource (lib "eagle-import") (part "R-US_R1206"))
    )
    (comp (ref "R62")
      (value "1k")
      (footprint "eagle-import:R0402")
      (libsource (lib "eagle-import") (part "R-US_R0402"))
    )
    (comp (ref "R63")
      (value "10k")
      (footprint "eagle-import:R0402")
      (libsource (lib "eagle-import") (part "R-US_R0402"))
    )
    (comp (ref "R64")
      (value "8.1k")
      (footprint "eagle-import:R0402")
      (libsource (lib "eagle-import") (part "R-US_R0402"))
    )
    (comp (ref "R65")
      (value "10k")
      (footprint "eagle-import:R0402")
      (libsource (lib "eagle-import") (part "R-US_R0402"))
    )
    (comp (ref "R66")
      (value "51k")
      (footprint "eagle-import:R0402")
      (libsource (lib "eagle-import") (part "R-US_R0402"))
    )
    (comp (ref "R67")
      (value "2.7k")
      (footprint "eagle-import:R0402")
      (libsource (lib "eagle-import") (part "R-US_R0402"))
    )
    (comp (ref "R68")
      (value "20k")
      (footprint "eagle-import:R0402")
      (libsource (lib "eagle-import") (part "R-US_R0402"))
    )
    (comp (ref "R69")
      (value "1k")
      (footprint "eagle-import:R0402")
      (libsource (lib "eagle-import") (part "R-US_R0402"))
    )
    (comp (ref "R70")
      (value "20k")
      (footprint "eagle-import:R0402")
      (libsource (lib "eagle-import") (part "R-US_R0402"))
    )
    (comp (ref "R71")
      (value "1k")
      (footprint "eagle-import:R0402")
      (libsource (lib "eagle-import") (part "R-US_R0402"))
    )
    (comp (ref "R72")
      (value "20k")
      (footprint "eagle-import:R0402")
      (libsource (lib "eagle-import") (part "R-US_R0402"))
    )
    (comp (ref "R73")
      (value "100m")
      (footprint "eagle-import:R1206")
      (libsource (lib "eagle-import") (part "R-US_R1206"))
    )
    (comp (ref "R74")
      (value "1k")
      (footprint "eagle-import:R0402")
      (libsource (lib "eagle-import") (part "R-US_R0402"))
    )
    (comp (ref "R75")
      (value "1k")
      (footprint "eagle-import:R0402")
      (libsource (lib "eagle-import") (part "R-US_R0402"))
    )
    (comp (ref "R76")
      (value "1k")
      (footprint "eagle-import:R0402")
      (libsource (lib "eagle-import") (part "R-US_R0402"))
    )
    (comp (ref "R77")
      (value "1k")
      (footprint "eagle-import:R0402")
      (libsource (lib "eagle-import") (part "R-US_R0402"))
    )
    (comp (ref "R78")
      (value "1k")
      (footprint "eagle-import:R0402")
      (libsource (lib "eagle-import") (part "R-US_R0402"))
    )
    (comp (ref "R79")
      (value "10k")
      (footprint "eagle-import:R0402")
      (libsource (lib "eagle-import") (part "R-US_R0402"))
    )
    (comp (ref "R80")
      (value "10k")
      (footprint "eagle-import:R0402")
      (libsource (lib "eagle-import") (part "R-US_R0402"))
    )
    (comp (ref "R81")
      (value "10k")
      (footprint "eagle-import:R0402")
      (libsource (lib "eagle-import") (part "R-US_R0402"))
    )
    (comp (ref "R82")
      (value "10k")
      (footprint "eagle-import:R0402")
      (libsource (lib "eagle-import") (part "R-US_R0402"))
    )
    (comp (ref "R83")
      (value "10k")
      (footprint "eagle-import:R0402")
      (libsource (lib "eagle-import") (part "R-US_R0402"))
    )
    (comp (ref "R84")
      (value "10k")
      (footprint "eagle-import:R0402")
      (libsource (lib "eagle-import") (part "R-US_R0402"))
    )
    (comp (ref "R85")
      (value "10k")
      (footprint "eagle-import:R0402")
      (libsource (lib "eagle-import") (part "R-US_R0402"))
    )
    (comp (ref "R86")
      (value "100m")
      (footprint "eagle-import:R1206")
      (libsource (lib "eagle-import") (part "R-US_R1206"))
    )
    (comp (ref "R87")
      (value "10k")
      (footprint "eagle-import:R0402")
      (libsource (lib "eagle-import") (part "R-US_R0402"))
    )
    (comp (ref "R88")
      (value "8.1k")
      (footprint "eagle-import:R0402")
      (libsource (lib "eagle-import") (part "R-US_R0402"))
    )
    (comp (ref "R89")
      (value "10k")
      (footprint "eagle-import:R0402")
      (libsource (lib "eagle-import") (part "R-US_R0402"))
    )
    (comp (ref "R90")
      (value "1k")
      (footprint "eagle-import:R0402")
      (libsource (lib "eagle-import") (part "R-US_R0402"))
    )
    (comp (ref "R91")
      (value "20k")
      (footprint "eagle-import:R0402")
      (libsource (lib "eagle-import") (part "R-US_R0402"))
    )
    (comp (ref "R92")
      (value "1k")
      (footprint "eagle-import:R0402")
      (libsource (lib "eagle-import") (part "R-US_R0402"))
    )
    (comp (ref "R93")
      (value "20k")
      (footprint "eagle-import:R0402")
      (libsource (lib "eagle-import") (part "R-US_R0402"))
    )
    (comp (ref "R94")
      (value "100m")
      (footprint "eagle-import:R1206")
      (libsource (lib "eagle-import") (part "R-US_R1206"))
    )
    (comp (ref "R95")
      (value "10k")
      (footprint "eagle-import:R0402")
      (libsource (lib "eagle-import") (part "R-US_R0402"))
    )
    (comp (ref "R96")
      (value "10k")
      (footprint "eagle-import:R0402")
      (libsource (lib "eagle-import") (part "R-US_R0402"))
    )
    (comp (ref "R97")
      (value "10k")
      (footprint "eagle-import:R0402")
      (libsource (lib "eagle-import") (part "R-US_R0402"))
    )
    (comp (ref "R98")
      (value "10k")
      (footprint "eagle-import:R0402")
      (libsource (lib "eagle-import") (part "R-US_R0402"))
    )
    (comp (ref "R99")
      (value "10k")
      (footprint "eagle-import:R0402")
      (libsource (lib "eagle-import") (part "R-US_R0402"))
    )
    (comp (ref "R100")
      (value "10k")
      (footprint "eagle-import:R0402")
      (libsource (lib "eagle-import") (part "R-US_R0402"))
    )
    (comp (ref "R101")
      (value "10k")
      (footprint "eagle-import:R0402")
      (libsource (lib "eagle-import") (part "R-US_R0402"))
    )
    (comp (ref "R102")
      (value "10k")
      (footprint "eagle-import:R0402")
      (libsource (lib "eagle-import") (part "R-US_R0402"))
    )
    (comp (ref "R103")
      (value "10k")
      (footprint "eagle-import:R0402")
      (libsource (lib "eagle-import") (part "R-US_R0402"))
    )
    (comp (ref "R104")
      (value "10k")
      (footprint "eagle-import:R0402")
      (libsource (lib "eagle-import") (part "R-US_R0402"))
    )
    (comp (ref "R105")
      (value "10k")
      (footprint "eagle-import:R0402")
      (libsource (lib "eagle-import") (part "R-US_R0402"))
    )
    (comp (ref "R106")
      (value "10k")
      (footprint "eagle-import:R0402")
      (libsource (lib "eagle-import") (part "R-US_R0402"))
    )
    (comp (ref "R107")
      (value "10k")
      (footprint "eagle-import:R0402")
      (libsource (lib "eagle-import") (part "R-US_R0402"))
    )
    (comp (ref "R108")
      (value "10k")
      (footprint "eagle-import:R0402")
      (libsource (lib "eagle-import") (part "R-US_R0402"))
    )
    (comp (ref "R109")
      (value "10k")
      (footprint "eagle-import:R0402")
      (libsource (lib "eagle-import") (part "R-US_R0402"))
    )
    (comp (ref "R110")
      (value "10k")
      (footprint "eagle-import:R0402")
      (libsource (lib "eagle-import") (part "R-US_R0402"))
    )
    (comp (ref "R111")
      (value "10k")
      (footprint "eagle-import:R0402")
      (libsource (lib "eagle-import") (part "R-US_R0402"))
    )
    (comp (ref "R112")
      (value "10k")
      (footprint "eagle-import:R0402")
      (libsource (lib "eagle-import") (part "R-US_R0402"))
    )
    (comp (ref "R113")
      (value "33k")
      (footprint "eagle-import:R0402")
      (libsource (lib "eagle-import") (part "R-US_R0402"))
    )
    (comp (ref "R114")
      (value "10k")
      (footprint "eagle-import:R0402")
      (libsource (lib "eagle-import") (part "R-US_R0402"))
    )
    (comp (ref "U1")
      (value "MCP6002SOIC")
      (footprint "eagle-import:8-SOIC")
      (libsource (lib "eagle-import") (part "MCP6002SOIC"))
    )
    (comp (ref "U2")
      (value "CJ431")
      (footprint "eagle-import:SOT23")
      (libsource (lib "eagle-import") (part "TL431SOT23"))
    )
    (comp (ref "U3")
      (value "3.3V")
      (footprint "eagle-import:SOT-89")
      (libsource (lib "eagle-import") (part "AP1117UR133-B"))
    )
    (comp (ref "U4")
      (value "FP6291")
      (footprint "eagle-import:SOT23-6")
      (libsource (lib "eagle-import") (part "FP6291"))
    )
    (comp (ref "U5")
      (value "STM32_BLUE_PILL")
      (footprint "eagle-import:STM32_BLUE_PILL_USABLE")
      (libsource (lib "eagle-import") (part "STM32_BLUE_PILL"))
    )
    (comp (ref "U6")
      (value "CJ431")
      (footprint "eagle-import:SOT23")
      (libsource (lib "eagle-import") (part "TL431SOT23"))
    )
    (comp (ref "U7")
      (value "STM32_BLUE_PILL")
      (footprint "eagle-import:STM32_BLUE_PILL_USABLE")
      (libsource (lib "eagle-import") (part "STM32_BLUE_PILL"))
    )
    (comp (ref "U8")
      (value "3.3V")
      (footprint "eagle-import:SOT-89")
      (libsource (lib "eagle-import") (part "AP1117UR133-B"))
    )
    (comp (ref "U9")
      (value "FP6291")
      (footprint "eagle-import:SOT23-6")
      (libsource (lib "eagle-import") (part "FP6291"))
    )
    (comp (ref "U10")
      (value "MCP6002SOIC")
      (footprint "eagle-import:8-SOIC")
      (libsource (lib "eagle-import") (part "MCP6002SOIC"))
    )
  )
  (nets
    (net (code "1") (name "2V495") (class "Default")
      (node (ref "C19") (pin "1") (pinfunction "1_1") (pintype "passive"))
      (node (ref "C22") (pin "1") (pinfunction "1_1") (pintype "passive"))
      (node (ref "R18") (pin "2") (pinfunction "2_2") (pintype "passive"))
      (node (ref "R30") (pin "2") (pinfunction "2_2") (pintype "passive"))
      (node (ref "R58") (pin "2") (pinfunction "2_2") (pintype "passive"))
      (node (ref "R59") (pin "2") (pinfunction "2_2") (pintype "passive"))
      (node (ref "R85") (pin "2") (pinfunction "2_2") (pintype "passive"))
      (node (ref "R9") (pin "2") (pinfunction "2_2") (pintype "passive"))
      (node (ref "U2") (pin "1") (pinfunction "K_1") (pintype "passive"))
      (node (ref "U2") (pin "2") (pinfunction "REF_2") (pintype "passive"))
      (node (ref "U5") (pin "A5") (pinfunction "A5_A5") (pintype "bidirectional"))
      (node (ref "U6") (pin "1") (pinfunction "K_1") (pintype "passive"))
      (node (ref "U6") (pin "2") (pinfunction "REF_2") (pintype "passive"))
      (node (ref "U7") (pin "A5") (pinfunction "A5_A5") (pintype "bidirectional"))
    )
    (net (code "2") (name "3V3") (class "Default")
      (node (ref "C17") (pin "1") (pinfunction "1_1") (pintype "passive"))
      (node (ref "C18") (pin "1") (pinfunction "1_1") (pintype "passive"))
      (node (ref "C21") (pin "1") (pinfunction "1_1") (pintype "passive"))
      (node (ref "C24") (pin "1") (pinfunction "1_1") (pintype "passive"))
      (node (ref "JP18") (pin "3") (pinfunction "3_3") (pintype "passive"))
      (node (ref "JP21") (pin "3") (pinfunction "3_3") (pintype "passive"))
      (node (ref "JP24") (pin "3") (pinfunction "3_3") (pintype "passive"))
      (node (ref "JP28") (pin "2") (pinfunction "2_2") (pintype "passive"))
      (node (ref "JP30") (pin "3") (pinfunction "3_3") (pintype "passive"))
      (node (ref "JP33") (pin "3") (pinfunction "3_3") (pintype "passive"))
      (node (ref "JP36") (pin "3") (pinfunction "3_3") (pintype "passive"))
      (node (ref "JP38") (pin "3") (pinfunction "3_3") (pintype "passive"))
      (node (ref "JP40") (pin "3") (pinfunction "3_3") (pintype "passive"))
      (node (ref "JP42") (pin "3") (pinfunction "3_3") (pintype "passive"))
      (node (ref "JP44") (pin "3") (pinfunction "3_3") (pintype "passive"))
      (node (ref "JP46") (pin "3") (pinfunction "3_3") (pintype "passive"))
      (node (ref "JP48") (pin "3") (pinfunction "3_3") (pintype "passive"))
      (node (ref "JP65") (pin "2") (pinfunction "2_2") (pintype "passive"))
      (node (ref "R42") (pin "1") (pinfunction "1_1") (pintype "passive"))
      (node (ref "R60") (pin "1") (pinfunction "1_1") (pintype "passive"))
      (node (ref "U3") (pin "1") (pinfunction "VO_1") (pintype "bidirectional"))
      (node (ref "U5") (pin "3V3") (pinfunction "3V3_3V3") (pintype "bidirectional"))
      (node (ref "U5") (pin "3V3_2") (pinfunction "3V3_2_3V3_2") (pintype "bidirectional"))
      (node (ref "U7") (pin "3V3") (pinfunction "3V3_3V3") (pintype "bidirectional"))
      (node (ref "U7") (pin "3V3_2") (pinfunction "3V3_2_3V3_2") (pintype "bidirectional"))
      (node (ref "U8") (pin "1") (pinfunction "VO_1") (pintype "bidirectional"))
    )
    (net (code "3") (name "12V") (class "Default")
      (node (ref "C12") (pin "1") (pinfunction "1_1") (pintype "passive"))
      (node (ref "C13") (pin "1") (pinfunction "1_1") (pintype "passive"))
      (node (ref "C15") (pin "1") (pinfunction "1_1") (pintype "passive"))
      (node (ref "C28") (pin "1") (pinfunction "1_1") (pintype "passive"))
      (node (ref "C31") (pin "1") (pinfunction "1_1") (pintype "passive"))
      (node (ref "C32") (pin "1") (pinfunction "1_1") (pintype "passive"))
      (node (ref "D11") (pin "K") (pinfunction "CATHODE_K") (pintype "passive"))
      (node (ref "D21") (pin "K") (pinfunction "CATHODE_K") (pintype "passive"))
      (node (ref "JP1") (pin "3") (pinfunction "3_3") (pintype "passive"))
      (node (ref "JP10") (pin "3") (pinfunction "3_3") (pintype "passive"))
      (node (ref "JP13") (pin "3") (pinfunction "3_3") (pintype "passive"))
      (node (ref "JP17") (pin "3") (pinfunction "3_3") (pintype "passive"))
      (node (ref "JP28") (pin "4") (pinfunction "4_4") (pintype "passive"))
      (node (ref "JP29") (pin "3") (pinfunction "3_3") (pintype "passive"))
      (node (ref "JP4") (pin "3") (pinfunction "3_3") (pintype "passive"))
      (node (ref "JP65") (pin "4") (pinfunction "4_4") (pintype "passive"))
      (node (ref "JP66") (pin "3") (pinfunction "3_3") (pintype "passive"))
      (node (ref "JP67") (pin "3") (pinfunction "3_3") (pintype "passive"))
      (node (ref "JP68") (pin "3") (pinfunction "3_3") (pintype "passive"))
      (node (ref "JP69") (pin "3") (pinfunction "3_3") (pintype "passive"))
      (node (ref "JP7") (pin "3") (pinfunction "3_3") (pintype "passive"))
      (node (ref "JP70") (pin "3") (pinfunction "3_3") (pintype "passive"))
      (node (ref "JP71") (pin "3") (pinfunction "3_3") (pintype "passive"))
      (node (ref "JP72") (pin "3") (pinfunction "3_3") (pintype "passive"))
      (node (ref "Q1") (pin "2") (pinfunction "S_2") (pintype "bidirectional"))
      (node (ref "Q11") (pin "2") (pinfunction "S_2") (pintype "bidirectional"))
      (node (ref "Q13") (pin "2") (pinfunction "S_2") (pintype "bidirectional"))
      (node (ref "Q16") (pin "2") (pinfunction "S_2") (pintype "bidirectional"))
      (node (ref "Q21") (pin "2") (pinfunction "S_2") (pintype "bidirectional"))
      (node (ref "Q33") (pin "2") (pinfunction "S_2") (pintype "bidirectional"))
      (node (ref "Q37") (pin "2") (pinfunction "S_2") (pintype "bidirectional"))
      (node (ref "Q39") (pin "2") (pinfunction "S_2") (pintype "bidirectional"))
      (node (ref "Q41") (pin "2") (pinfunction "S_2") (pintype "bidirectional"))
      (node (ref "Q43") (pin "2") (pinfunction "S_2") (pintype "bidirectional"))
      (node (ref "Q45") (pin "2") (pinfunction "S_2") (pintype "bidirectional"))
      (node (ref "Q47") (pin "2") (pinfunction "S_2") (pintype "bidirectional"))
      (node (ref "Q5") (pin "2") (pinfunction "S_2") (pintype "bidirectional"))
      (node (ref "Q7") (pin "2") (pinfunction "S_2") (pintype "bidirectional"))
      (node (ref "R100") (pin "1") (pinfunction "1_1") (pintype "passive"))
      (node (ref "R102") (pin "1") (pinfunction "1_1") (pintype "passive"))
      (node (ref "R104") (pin "1") (pinfunction "1_1") (pintype "passive"))
      (node (ref "R106") (pin "1") (pinfunction "1_1") (pintype "passive"))
      (node (ref "R108") (pin "1") (pinfunction "1_1") (pintype "passive"))
      (node (ref "R110") (pin "1") (pinfunction "1_1") (pintype "passive"))
      (node (ref "R113") (pin "2") (pinfunction "2_2") (pintype "passive"))
      (node (ref "R15") (pin "1") (pinfunction "1_1") (pintype "passive"))
      (node (ref "R19") (pin "1") (pinfunction "1_1") (pintype "passive"))
      (node (ref "R25") (pin "1") (pinfunction "1_1") (pintype "passive"))
      (node (ref "R33") (pin "2") (pinfunction "2_2") (pintype "passive"))
      (node (ref "R38") (pin "1") (pinfunction "1_1") (pintype "passive"))
      (node (ref "R39") (pin "2") (pinfunction "2_2") (pintype "passive"))
      (node (ref "R47") (pin "1") (pinfunction "1_1") (pintype "passive"))
      (node (ref "R5") (pin "1") (pinfunction "1_1") (pintype "passive"))
      (node (ref "R55") (pin "1") (pinfunction "1_1") (pintype "passive"))
      (node (ref "R66") (pin "2") (pinfunction "2_2") (pintype "passive"))
      (node (ref "R98") (pin "1") (pinfunction "1_1") (pintype "passive"))
    )
    (net (code "4") (name "12VSNS") (class "Default")
      (node (ref "C10") (pin "1") (pinfunction "1_1") (pintype "passive"))
      (node (ref "C38") (pin "1") (pinfunction "1_1") (pintype "passive"))
      (node (ref "R113") (pin "1") (pinfunction "1_1") (pintype "passive"))
      (node (ref "R114") (pin "2") (pinfunction "2_2") (pintype "passive"))
      (node (ref "R31") (pin "2") (pinfunction "2_2") (pintype "passive"))
      (node (ref "R33") (pin "1") (pinfunction "1_1") (pintype "passive"))
      (node (ref "U5") (pin "A4") (pinfunction "A4_A4") (pintype "bidirectional"))
      (node (ref "U7") (pin "A4") (pinfunction "A4_A4") (pintype "bidirectional"))
    )
    (net (code "5") (name "AUXADC1") (class "Default")
      (node (ref "JP26") (pin "3") (pinfunction "3_3") (pintype "passive"))
      (node (ref "JP63") (pin "3") (pinfunction "3_3") (pintype "passive"))
      (node (ref "U5") (pin "A1") (pinfunction "A1_A1") (pintype "bidirectional"))
      (node (ref "U7") (pin "A1") (pinfunction "A1_A1") (pintype "bidirectional"))
    )
    (net (code "6") (name "AUXADC2") (class "Default")
      (node (ref "JP26") (pin "2") (pinfunction "2_2") (pintype "passive"))
      (node (ref "JP63") (pin "2") (pinfunction "2_2") (pintype "passive"))
      (node (ref "U5") (pin "A0") (pinfunction "A0_A0") (pintype "bidirectional"))
      (node (ref "U7") (pin "A0") (pinfunction "A0_A0") (pintype "bidirectional"))
    )
    (net (code "7") (name "AUXI3") (class "Default")
      (node (ref "JP26") (pin "1") (pinfunction "1_1") (pintype "passive"))
      (node (ref "JP63") (pin "1") (pinfunction "1_1") (pintype "passive"))
      (node (ref "U5") (pin "C13") (pinfunction "C13_C13") (pintype "bidirectional"))
      (node (ref "U7") (pin "C13") (pinfunction "C13_C13") (pintype "bidirectional"))
    )
    (net (code "8") (name "AUXIO1") (class "Default")
      (node (ref "JP25") (pin "2") (pinfunction "2_2") (pintype "passive"))
      (node (ref "JP64") (pin "2") (pinfunction "2_2") (pintype "passive"))
      (node (ref "U5") (pin "B8") (pinfunction "B8_B8") (pintype "bidirectional"))
      (node (ref "U7") (pin "B8") (pinfunction "B8_B8") (pintype "bidirectional"))
    )
    (net (code "9") (name "AUXIO2") (class "Default")
      (node (ref "JP25") (pin "1") (pinfunction "1_1") (pintype "passive"))
      (node (ref "JP64") (pin "1") (pinfunction "1_1") (pintype "passive"))
      (node (ref "U5") (pin "B9") (pinfunction "B9_B9") (pintype "bidirectional"))
      (node (ref "U7") (pin "B9") (pinfunction "B9_B9") (pintype "bidirectional"))
    )
    (net (code "10") (name "D+2P0") (class "Default")
      (node (ref "CON1") (pin "3-D+") (pinfunction "D+_3-D+") (pintype "bidirectional"))
      (node (ref "CON2") (pin "3-D+") (pinfunction "D+_3-D+") (pintype "bidirectional"))
      (node (ref "CON5") (pin "3-D+") (pinfunction "D+_3-D+") (pintype "bidirectional"))
      (node (ref "CON6") (pin "3-D+") (pinfunction "D+_3-D+") (pintype "bidirectional"))
    )
    (net (code "11") (name "D+3P0") (class "Default")
      (node (ref "CON3") (pin "3-D+") (pinfunction "D+_3-D+") (pintype "bidirectional"))
      (node (ref "CON4") (pin "3-D+") (pinfunction "D+_3-D+") (pintype "bidirectional"))
      (node (ref "CON7") (pin "3-D+") (pinfunction "D+_3-D+") (pintype "bidirectional"))
      (node (ref "CON8") (pin "3-D+") (pinfunction "D+_3-D+") (pintype "bidirectional"))
    )
    (net (code "12") (name "D-2P0") (class "Default")
      (node (ref "CON1") (pin "2-D-") (pinfunction "D-_2-D-") (pintype "bidirectional"))
      (node (ref "CON2") (pin "2-D-") (pinfunction "D-_2-D-") (pintype "bidirectional"))
      (node (ref "CON5") (pin "2-D-") (pinfunction "D-_2-D-") (pintype "bidirectional"))
      (node (ref "CON6") (pin "2-D-") (pinfunction "D-_2-D-") (pintype "bidirectional"))
    )
    (net (code "13") (name "D-3P0") (class "Default")
      (node (ref "CON3") (pin "2-D-") (pinfunction "D-_2-D-") (pintype "bidirectional"))
      (node (ref "CON4") (pin "2-D-") (pinfunction "D-_2-D-") (pintype "bidirectional"))
      (node (ref "CON7") (pin "2-D-") (pinfunction "D-_2-D-") (pintype "bidirectional"))
      (node (ref "CON8") (pin "2-D-") (pinfunction "D-_2-D-") (pintype "bidirectional"))
    )
    (net (code "14") (name "GND") (class "Default")
      (node (ref "C1") (pin "2") (pinfunction "2_2") (pintype "passive"))
      (node (ref "C10") (pin "2") (pinfunction "2_2") (pintype "passive"))
      (node (ref "C11") (pin "2") (pinfunction "2_2") (pintype "passive"))
      (node (ref "C12") (pin "2") (pinfunction "2_2") (pintype "passive"))
      (node (ref "C13") (pin "2") (pinfunction "2_2") (pintype "passive"))
      (node (ref "C14") (pin "2") (pinfunction "2_2") (pintype "passive"))
      (node (ref "C15") (pin "2") (pinfunction "2_2") (pintype "passive"))
      (node (ref "C16") (pin "2") (pinfunction "2_2") (pintype "passive"))
      (node (ref "C17") (pin "2") (pinfunction "2_2") (pintype "passive"))
      (node (ref "C18") (pin "2") (pinfunction "2_2") (pintype "passive"))
      (node (ref "C19") (pin "2") (pinfunction "2_2") (pintype "passive"))
      (node (ref "C2") (pin "2") (pinfunction "2_2") (pintype "passive"))
      (node (ref "C20") (pin "2") (pinfunction "2_2") (pintype "passive"))
      (node (ref "C21") (pin "2") (pinfunction "2_2") (pintype "passive"))
      (node (ref "C22") (pin "2") (pinfunction "2_2") (pintype "passive"))
      (node (ref "C23") (pin "2") (pinfunction "2_2") (pintype "passive"))
      (node (ref "C24") (pin "2") (pinfunction "2_2") (pintype "passive"))
      (node (ref "C25") (pin "2") (pinfunction "2_2") (pintype "passive"))
      (node (ref "C26") (pin "2") (pinfunction "2_2") (pintype "passive"))
      (node (ref "C27") (pin "2") (pinfunction "2_2") (pintype "passive"))
      (node (ref "C28") (pin "2") (pinfunction "2_2") (pintype "passive"))
      (node (ref "C29") (pin "2") (pinfunction "2_2") (pintype "passive"))
      (node (ref "C3") (pin "2") (pinfunction "2_2") (pintype "passive"))
      (node (ref "C30") (pin "2") (pinfunction "2_2") (pintype "passive"))
      (node (ref "C31") (pin "2") (pinfunction "2_2") (pintype "passive"))
      (node (ref "C32") (pin "2") (pinfunction "2_2") (pintype "passive"))
      (node (ref "C33") (pin "2") (pinfunction "2_2") (pintype "passive"))
      (node (ref "C34") (pin "2") (pinfunction "2_2") (pintype "passive"))
      (node (ref "C35") (pin "2") (pinfunction "2_2") (pintype "passive"))
      (node (ref "C36") (pin "2") (pinfunction "2_2") (pintype "passive"))
      (node (ref "C37") (pin "2") (pinfunction "2_2") (pintype "passive"))
      (node (ref "C38") (pin "2") (pinfunction "2_2") (pintype "passive"))
      (node (ref "C4") (pin "2") (pinfunction "2_2") (pintype "passive"))
      (node (ref "C5") (pin "2") (pinfunction "2_2") (pintype "passive"))
      (node (ref "C6") (pin "2") (pinfunction "2_2") (pintype "passive"))
      (node (ref "C7") (pin "2") (pinfunction "2_2") (pintype "passive"))
      (node (ref "C8") (pin "2") (pinfunction "2_2") (pintype "passive"))
      (node (ref "C9") (pin "2") (pinfunction "2_2") (pintype "passive"))
      (node (ref "CON1") (pin "4-GND") (pinfunction "GND_4-GND") (pintype "bidirectional"))
      (node (ref "CON2") (pin "5-GND") (pinfunction "GND_5-GND") (pintype "bidirectional"))
      (node (ref "CON3") (pin "4-GND") (pinfunction "GND_4-GND") (pintype "bidirectional"))
      (node (ref "CON3") (pin "7-GND") (pinfunction "GND_D_7-GND") (pintype "bidirectional"))
      (node (ref "CON4") (pin "4-GND") (pinfunction "GND_4-GND") (pintype "bidirectional"))
      (node (ref "CON4") (pin "7-GNDD") (pinfunction "GND_D_7-GNDD") (pintype "bidirectional"))
      (node (ref "CON5") (pin "5-GND") (pinfunction "GND_5-GND") (pintype "bidirectional"))
      (node (ref "CON6") (pin "4-GND") (pinfunction "GND_4-GND") (pintype "bidirectional"))
      (node (ref "CON7") (pin "4-GND") (pinfunction "GND_4-GND") (pintype "bidirectional"))
      (node (ref "CON7") (pin "7-GNDD") (pinfunction "GND_D_7-GNDD") (pintype "bidirectional"))
      (node (ref "CON8") (pin "4-GND") (pinfunction "GND_4-GND") (pintype "bidirectional"))
      (node (ref "CON8") (pin "7-GND") (pinfunction "GND_D_7-GND") (pintype "bidirectional"))
      (node (ref "J1") (pin "1") (pinfunction "1_1") (pintype "passive"))
      (node (ref "J2") (pin "1") (pinfunction "1_1") (pintype "passive"))
      (node (ref "J3") (pin "1") (pinfunction "1_1") (pintype "passive"))
      (node (ref "J4") (pin "1") (pinfunction "1_1") (pintype "passive"))
      (node (ref "JP12") (pin "1") (pinfunction "1_1") (pintype "passive"))
      (node (ref "JP15") (pin "1") (pinfunction "1_1") (pintype "passive"))
      (node (ref "JP16") (pin "1") (pinfunction "1_1") (pintype "passive"))
      (node (ref "JP20") (pin "1") (pinfunction "1_1") (pintype "passive"))
      (node (ref "JP22") (pin "1") (pinfunction "1_1") (pintype "passive"))
      (node (ref "JP23") (pin "1") (pinfunction "1_1") (pintype "passive"))
      (node (ref "JP27") (pin "1") (pinfunction "1_1") (pintype "passive"))
      (node (ref "JP28") (pin "1") (pinfunction "1_1") (pintype "passive"))
      (node (ref "JP3") (pin "1") (pinfunction "1_1") (pintype "passive"))
      (node (ref "JP32") (pin "1") (pinfunction "1_1") (pintype "passive"))
      (node (ref "JP34") (pin "1") (pinfunction "1_1") (pintype "passive"))
      (node (ref "JP35") (pin "1") (pinfunction "1_1") (pintype "passive"))
      (node (ref "JP37") (pin "1") (pinfunction "1_1") (pintype "passive"))
      (node (ref "JP39") (pin "1") (pinfunction "1_1") (pintype "passive"))
      (node (ref "JP41") (pin "1") (pinfunction "1_1") (pintype "passive"))
      (node (ref "JP43") (pin "1") (pinfunction "1_1") (pintype "passive"))
      (node (ref "JP45") (pin "1") (pinfunction "1_1") (pintype "passive"))
      (node (ref "JP47") (pin "1") (pinfunction "1_1") (pintype "passive"))
      (node (ref "JP50") (pin "1") (pinfunction "1_1") (pintype "passive"))
      (node (ref "JP52") (pin "1") (pinfunction "1_1") (pintype "passive"))
      (node (ref "JP54") (pin "1") (pinfunction "1_1") (pintype "passive"))
      (node (ref "JP56") (pin "1") (pinfunction "1_1") (pintype "passive"))
      (node (ref "JP58") (pin "1") (pinfunction "1_1") (pintype "passive"))
      (node (ref "JP6") (pin "1") (pinfunction "1_1") (pintype "passive"))
      (node (ref "JP60") (pin "1") (pinfunction "1_1") (pintype "passive"))
      (node (ref "JP62") (pin "1") (pinfunction "1_1") (pintype "passive"))
      (node (ref "JP65") (pin "1") (pinfunction "1_1") (pintype "passive"))
      (node (ref "JP9") (pin "1") (pinfunction "1_1") (pintype "passive"))
      (node (ref "Q10") (pin "2") (pinfunction "S_2") (pintype "bidirectional"))
      (node (ref "Q12") (pin "2") (pinfunction "S_2") (pintype "bidirectional"))
      (node (ref "Q14") (pin "2") (pinfunction "S_2") (pintype "bidirectional"))
      (node (ref "Q15") (pin "2") (pinfunction "S_2") (pintype "bidirectional"))
      (node (ref "Q17") (pin "2") (pinfunction "S_2") (pintype "bidirectional"))
      (node (ref "Q18") (pin "2") (pinfunction "S_2") (pintype "bidirectional"))
      (node (ref "Q19") (pin "2") (pinfunction "S_2") (pintype "bidirectional"))
      (node (ref "Q2") (pin "2") (pinfunction "S_2") (pintype "bidirectional"))
      (node (ref "Q20") (pin "2") (pinfunction "S_2") (pintype "bidirectional"))
      (node (ref "Q22") (pin "2") (pinfunction "S_2") (pintype "bidirectional"))
      (node (ref "Q23") (pin "2") (pinfunction "S_2") (pintype "bidirectional"))
      (node (ref "Q24") (pin "2") (pinfunction "S_2") (pintype "bidirectional"))
      (node (ref "Q25") (pin "2") (pinfunction "S_2") (pintype "bidirectional"))
      (node (ref "Q27") (pin "2") (pinfunction "S_2") (pintype "bidirectional"))
      (node (ref "Q28") (pin "2") (pinfunction "S_2") (pintype "bidirectional"))
      (node (ref "Q29") (pin "2") (pinfunction "S_2") (pintype "bidirectional"))
      (node (ref "Q30") (pin "2") (pinfunction "S_2") (pintype "bidirectional"))
      (node (ref "Q31") (pin "2") (pinfunction "S_2") (pintype "bidirectional"))
      (node (ref "Q32") (pin "2") (pinfunction "S_2") (pintype "bidirectional"))
      (node (ref "Q35") (pin "2") (pinfunction "S_2") (pintype "bidirectional"))
      (node (ref "Q36") (pin "2") (pinfunction "S_2") (pintype "bidirectional"))
      (node (ref "Q38") (pin "2") (pinfunction "S_2") (pintype "bidirectional"))
      (node (ref "Q4") (pin "2") (pinfunction "S_2") (pintype "bidirectional"))
      (node (ref "Q40") (pin "2") (pinfunction "S_2") (pintype "bidirectional"))
      (node (ref "Q42") (pin "2") (pinfunction "S_2") (pintype "bidirectional"))
      (node (ref "Q44") (pin "2") (pinfunction "S_2") (pintype "bidirectional"))
      (node (ref "Q46") (pin "2") (pinfunction "S_2") (pintype "bidirectional"))
      (node (ref "Q48") (pin "2") (pinfunction "S_2") (pintype "bidirectional"))
      (node (ref "Q6") (pin "2") (pinfunction "S_2") (pintype "bidirectional"))
      (node (ref "Q8") (pin "2") (pinfunction "S_2") (pintype "bidirectional"))
      (node (ref "R1") (pin "2") (pinfunction "2_2") (pintype "passive"))
      (node (ref "R101") (pin "1") (pinfunction "1_1") (pintype "passive"))
      (node (ref "R103") (pin "1") (pinfunction "1_1") (pintype "passive"))
      (node (ref "R105") (pin "1") (pinfunction "1_1") (pintype "passive"))
      (node (ref "R107") (pin "1") (pinfunction "1_1") (pintype "passive"))
      (node (ref "R109") (pin "1") (pinfunction "1_1") (pintype "passive"))
      (node (ref "R111") (pin "2") (pinfunction "2_2") (pintype "passive"))
      (node (ref "R112") (pin "2") (pinfunction "2_2") (pintype "passive"))
      (node (ref "R114") (pin "1") (pinfunction "1_1") (pintype "passive"))
      (node (ref "R12") (pin "1") (pinfunction "1_1") (pintype "passive"))
      (node (ref "R13") (pin "2") (pinfunction "2_2") (pintype "passive"))
      (node (ref "R17") (pin "1") (pinfunction "1_1") (pintype "passive"))
      (node (ref "R2") (pin "1") (pinfunction "1_1") (pintype "passive"))
      (node (ref "R20") (pin "2") (pinfunction "2_2") (pintype "passive"))
      (node (ref "R22") (pin "1") (pinfunction "1_1") (pintype "passive"))
      (node (ref "R23") (pin "1") (pinfunction "1_1") (pintype "passive"))
      (node (ref "R31") (pin "1") (pinfunction "1_1") (pintype "passive"))
      (node (ref "R32") (pin "2") (pinfunction "2_2") (pintype "passive"))
      (node (ref "R35") (pin "1") (pinfunction "1_1") (pintype "passive"))
      (node (ref "R36") (pin "1") (pinfunction "1_1") (pintype "passive"))
      (node (ref "R4") (pin "1") (pinfunction "1_1") (pintype "passive"))
      (node (ref "R40") (pin "1") (pinfunction "1_1") (pintype "passive"))
      (node (ref "R41") (pin "1") (pinfunction "1_1") (pintype "passive"))
      (node (ref "R44") (pin "1") (pinfunction "1_1") (pintype "passive"))
      (node (ref "R45") (pin "1") (pinfunction "1_1") (pintype "passive"))
      (node (ref "R48") (pin "1") (pinfunction "1_1") (pintype "passive"))
      (node (ref "R50") (pin "1") (pinfunction "1_1") (pintype "passive"))
      (node (ref "R52") (pin "1") (pinfunction "1_1") (pintype "passive"))
      (node (ref "R53") (pin "1") (pinfunction "1_1") (pintype "passive"))
      (node (ref "R56") (pin "1") (pinfunction "1_1") (pintype "passive"))
      (node (ref "R65") (pin "1") (pinfunction "1_1") (pintype "passive"))
      (node (ref "R67") (pin "1") (pinfunction "1_1") (pintype "passive"))
      (node (ref "R68") (pin "1") (pinfunction "1_1") (pintype "passive"))
      (node (ref "R70") (pin "2") (pinfunction "2_2") (pintype "passive"))
      (node (ref "R79") (pin "1") (pinfunction "1_1") (pintype "passive"))
      (node (ref "R80") (pin "1") (pinfunction "1_1") (pintype "passive"))
      (node (ref "R81") (pin "1") (pinfunction "1_1") (pintype "passive"))
      (node (ref "R82") (pin "1") (pinfunction "1_1") (pintype "passive"))
      (node (ref "R83") (pin "1") (pinfunction "1_1") (pintype "passive"))
      (node (ref "R84") (pin "1") (pinfunction "1_1") (pintype "passive"))
      (node (ref "R89") (pin "1") (pinfunction "1_1") (pintype "passive"))
      (node (ref "R91") (pin "2") (pinfunction "2_2") (pintype "passive"))
      (node (ref "R97") (pin "1") (pinfunction "1_1") (pintype "passive"))
      (node (ref "R99") (pin "1") (pinfunction "1_1") (pintype "passive"))
      (node (ref "U1") (pin "4") (pinfunction "GND_4") (pintype "power_in"))
      (node (ref "U10") (pin "4") (pinfunction "GND_4") (pintype "power_in"))
      (node (ref "U2") (pin "3") (pinfunction "A_3") (pintype "passive"))
      (node (ref "U3") (pin "2") (pinfunction "GND_2") (pintype "bidirectional"))
      (node (ref "U3") (pin "2@1") (pinfunction "GND_2@1") (pintype "bidirectional"))
      (node (ref "U4") (pin "2") (pinfunction "GND_2") (pintype "bidirectional"))
      (node (ref "U5") (pin "GND") (pinfunction "GND_GND") (pintype "bidirectional"))
      (node (ref "U5") (pin "GND2") (pinfunction "GND2_GND2") (pintype "bidirectional"))
      (node (ref "U5") (pin "GND4") (pinfunction "GND4_GND4") (pintype "bidirectional"))
      (node (ref "U6") (pin "3") (pinfunction "A_3") (pintype "passive"))
      (node (ref "U7") (pin "GND") (pinfunction "GND_GND") (pintype "bidirectional"))
      (node (ref "U7") (pin "GND2") (pinfunction "GND2_GND2") (pintype "bidirectional"))
      (node (ref "U7") (pin "GND4") (pinfunction "GND4_GND4") (pintype "bidirectional"))
      (node (ref "U8") (pin "2") (pinfunction "GND_2") (pintype "bidirectional"))
      (node (ref "U8") (pin "2@1") (pinfunction "GND_2@1") (pintype "bidirectional"))
      (node (ref "U9") (pin "2") (pinfunction "GND_2") (pintype "bidirectional"))
    )
    (net (code "15") (name "Net-(D1-ANODE)") (class "Default")
      (node (ref "D1") (pin "A") (pinfunction "ANODE_A") (pintype "passive"))
      (node (ref "JP2") (pin "2") (pinfunction "2_2") (pintype "passive"))
      (node (ref "JP3") (pin "2") (pinfunction "2_2") (pintype "passive"))
    )
    (net (code "16") (name "Net-(D1-CATHODE)") (class "Default")
      (node (ref "D1") (pin "K") (pinfunction "CATHODE_K") (pintype "passive"))
      (node (ref "JP1") (pin "2") (pinfunction "2_2") (pintype "passive"))
      (node (ref "JP2") (pin "1") (pinfunction "1_1") (pintype "passive"))
    )
    (net (code "17") (name "Net-(D5-ANODE)") (class "Default")
      (node (ref "D5") (pin "A") (pinfunction "ANODE_A") (pintype "passive"))
      (node (ref "JP5") (pin "2") (pinfunction "2_2") (pintype "passive"))
      (node (ref "JP6") (pin "2") (pinfunction "2_2") (pintype "passive"))
    )
    (net (code "18") (name "Net-(D5-CATHODE)") (class "Default")
      (node (ref "D5") (pin "K") (pinfunction "CATHODE_K") (pintype "passive"))
      (node (ref "JP4") (pin "2") (pinfunction "2_2") (pintype "passive"))
      (node (ref "JP5") (pin "1") (pinfunction "1_1") (pintype "passive"))
    )
    (net (code "19") (name "Net-(D6-ANODE)") (class "Default")
      (node (ref "D6") (pin "A") (pinfunction "ANODE_A") (pintype "passive"))
      (node (ref "JP8") (pin "2") (pinfunction "2_2") (pintype "passive"))
      (node (ref "JP9") (pin "2") (pinfunction "2_2") (pintype "passive"))
    )
    (net (code "20") (name "Net-(D6-CATHODE)") (class "Default")
      (node (ref "D6") (pin "K") (pinfunction "CATHODE_K") (pintype "passive"))
      (node (ref "JP7") (pin "2") (pinfunction "2_2") (pintype "passive"))
      (node (ref "JP8") (pin "1") (pinfunction "1_1") (pintype "passive"))
    )
    (net (code "21") (name "Net-(D7-CATHODE)") (class "Default")
      (node (ref "C7") (pin "1") (pinfunction "1_1") (pintype "passive"))
      (node (ref "C8") (pin "1") (pinfunction "1_1") (pintype "passive"))
      (node (ref "C9") (pin "1") (pinfunction "1_1") (pintype "passive"))
      (node (ref "D7") (pin "K") (pinfunction "CATHODE_K") (pintype "passive"))
      (node (ref "D8") (pin "K") (pinfunction "CATHODE_K") (pintype "passive"))
      (node (ref "D9") (pin "K") (pinfunction "CATHODE_K") (pintype "passive"))
      (node (ref "L1") (pin "1") (pinfunction "P$1_1") (pintype "passive"))
      (node (ref "U4") (pin "4") (pinfunction "EN_4") (pintype "bidirectional"))
      (node (ref "U4") (pin "5") (pinfunction "VCC_5") (pintype "bidirectional"))
    )
    (net (code "22") (name "Net-(D10-ANODE)") (class "Default")
      (node (ref "D10") (pin "A") (pinfunction "ANODE_A") (pintype "passive"))
      (node (ref "JP11") (pin "2") (pinfunction "2_2") (pintype "passive"))
      (node (ref "JP12") (pin "2") (pinfunction "2_2") (pintype "passive"))
    )
    (net (code "23") (name "Net-(D10-CATHODE)") (class "Default")
      (node (ref "D10") (pin "K") (pinfunction "CATHODE_K") (pintype "passive"))
      (node (ref "JP10") (pin "2") (pinfunction "2_2") (pintype "passive"))
      (node (ref "JP11") (pin "1") (pinfunction "1_1") (pintype "passive"))
    )
    (net (code "24") (name "Net-(D11-ANODE)") (class "Default")
      (node (ref "D11") (pin "A") (pinfunction "ANODE_A") (pintype "passive"))
      (node (ref "L1") (pin "2") (pinfunction "P$2_2") (pintype "passive"))
      (node (ref "U4") (pin "1") (pinfunction "LX_1") (pintype "bidirectional"))
    )
    (net (code "25") (name "Net-(D12-ANODE)") (class "Default")
      (node (ref "D12") (pin "A") (pinfunction "ANODE_A") (pintype "passive"))
      (node (ref "JP14") (pin "2") (pinfunction "2_2") (pintype "passive"))
      (node (ref "JP15") (pin "2") (pinfunction "2_2") (pintype "passive"))
    )
    (net (code "26") (name "Net-(D12-CATHODE)") (class "Default")
      (node (ref "D12") (pin "K") (pinfunction "CATHODE_K") (pintype "passive"))
      (node (ref "JP13") (pin "2") (pinfunction "2_2") (pintype "passive"))
      (node (ref "JP14") (pin "1") (pinfunction "1_1") (pintype "passive"))
    )
    (net (code "27") (name "Net-(D13-ANODE)") (class "Default")
      (node (ref "D13") (pin "A") (pinfunction "ANODE_A") (pintype "passive"))
      (node (ref "JP19") (pin "2") (pinfunction "2_2") (pintype "passive"))
      (node (ref "JP22") (pin "2") (pinfunction "2_2") (pintype "passive"))
    )
    (net (code "28") (name "Net-(D13-CATHODE)") (class "Default")
      (node (ref "D13") (pin "K") (pinfunction "CATHODE_K") (pintype "passive"))
      (node (ref "JP17") (pin "2") (pinfunction "2_2") (pintype "passive"))
      (node (ref "JP19") (pin "1") (pinfunction "1_1") (pintype "passive"))
    )
    (net (code "29") (name "Net-(D14-ANODE)") (class "Default")
      (node (ref "D14") (pin "A") (pinfunction "ANODE_A") (pintype "passive"))
      (node (ref "JP31") (pin "2") (pinfunction "2_2") (pintype "passive"))
      (node (ref "JP34") (pin "2") (pinfunction "2_2") (pintype "passive"))
    )
    (net (code "30") (name "Net-(D14-CATHODE)") (class "Default")
      (node (ref "D14") (pin "K") (pinfunction "CATHODE_K") (pintype "passive"))
      (node (ref "JP29") (pin "2") (pinfunction "2_2") (pintype "passive"))
      (node (ref "JP31") (pin "1") (pinfunction "1_1") (pintype "passive"))
    )
    (net (code "31") (name "Net-(D18-CATHODE)") (class "Default")
      (node (ref "C27") (pin "1") (pinfunction "1_1") (pintype "passive"))
      (node (ref "C29") (pin "1") (pinfunction "1_1") (pintype "passive"))
      (node (ref "C30") (pin "1") (pinfunction "1_1") (pintype "passive"))
      (node (ref "D18") (pin "K") (pinfunction "CATHODE_K") (pintype "passive"))
      (node (ref "D19") (pin "K") (pinfunction "CATHODE_K") (pintype "passive"))
      (node (ref "D20") (pin "K") (pinfunction "CATHODE_K") (pintype "passive"))
      (node (ref "L2") (pin "1") (pinfunction "P$1_1") (pintype "passive"))
      (node (ref "U9") (pin "4") (pinfunction "EN_4") (pintype "bidirectional"))
      (node (ref "U9") (pin "5") (pinfunction "VCC_5") (pintype "bidirectional"))
    )
    (net (code "32") (name "Net-(D21-ANODE)") (class "Default")
      (node (ref "D21") (pin "A") (pinfunction "ANODE_A") (pintype "passive"))
      (node (ref "L2") (pin "2") (pinfunction "P$2_2") (pintype "passive"))
      (node (ref "U9") (pin "1") (pinfunction "LX_1") (pintype "bidirectional"))
    )
    (net (code "33") (name "Net-(D22-ANODE)") (class "Default")
      (node (ref "D22") (pin "A") (pinfunction "ANODE_A") (pintype "passive"))
      (node (ref "JP49") (pin "2") (pinfunction "2_2") (pintype "passive"))
      (node (ref "JP50") (pin "2") (pinfunction "2_2") (pintype "passive"))
    )
    (net (code "34") (name "Net-(D22-CATHODE)") (class "Default")
      (node (ref "D22") (pin "K") (pinfunction "CATHODE_K") (pintype "passive"))
      (node (ref "JP49") (pin "1") (pinfunction "1_1") (pintype "passive"))
      (node (ref "JP66") (pin "2") (pinfunction "2_2") (pintype "passive"))
    )
    (net (code "35") (name "Net-(D23-ANODE)") (class "Default")
      (node (ref "D23") (pin "A") (pinfunction "ANODE_A") (pintype "passive"))
      (node (ref "JP51") (pin "2") (pinfunction "2_2") (pintype "passive"))
      (node (ref "JP52") (pin "2") (pinfunction "2_2") (pintype "passive"))
    )
    (net (code "36") (name "Net-(D23-CATHODE)") (class "Default")
      (node (ref "D23") (pin "K") (pinfunction "CATHODE_K") (pintype "passive"))
      (node (ref "JP51") (pin "1") (pinfunction "1_1") (pintype "passive"))
      (node (ref "JP67") (pin "2") (pinfunction "2_2") (pintype "passive"))
    )
    (net (code "37") (name "Net-(D24-ANODE)") (class "Default")
      (node (ref "D24") (pin "A") (pinfunction "ANODE_A") (pintype "passive"))
      (node (ref "JP53") (pin "2") (pinfunction "2_2") (pintype "passive"))
      (node (ref "JP54") (pin "2") (pinfunction "2_2") (pintype "passive"))
    )
    (net (code "38") (name "Net-(D24-CATHODE)") (class "Default")
      (node (ref "D24") (pin "K") (pinfunction "CATHODE_K") (pintype "passive"))
      (node (ref "JP53") (pin "1") (pinfunction "1_1") (pintype "passive"))
      (node (ref "JP68") (pin "2") (pinfunction "2_2") (pintype "passive"))
    )
    (net (code "39") (name "Net-(D25-ANODE)") (class "Default")
      (node (ref "D25") (pin "A") (pinfunction "ANODE_A") (pintype "passive"))
      (node (ref "JP55") (pin "2") (pinfunction "2_2") (pintype "passive"))
      (node (ref "JP56") (pin "2") (pinfunction "2_2") (pintype "passive"))
    )
    (net (code "40") (name "Net-(D25-CATHODE)") (class "Default")
      (node (ref "D25") (pin "K") (pinfunction "CATHODE_K") (pintype "passive"))
      (node (ref "JP55") (pin "1") (pinfunction "1_1") (pintype "passive"))
      (node (ref "JP69") (pin "2") (pinfunction "2_2") (pintype "passive"))
    )
    (net (code "41") (name "Net-(D26-ANODE)") (class "Default")
      (node (ref "D26") (pin "A") (pinfunction "ANODE_A") (pintype "passive"))
      (node (ref "JP57") (pin "2") (pinfunction "2_2") (pintype "passive"))
      (node (ref "JP58") (pin "2") (pinfunction "2_2") (pintype "passive"))
    )
    (net (code "42") (name "Net-(D26-CATHODE)") (class "Default")
      (node (ref "D26") (pin "K") (pinfunction "CATHODE_K") (pintype "passive"))
      (node (ref "JP57") (pin "1") (pinfunction "1_1") (pintype "passive"))
      (node (ref "JP70") (pin "2") (pinfunction "2_2") (pintype "passive"))
    )
    (net (code "43") (name "Net-(D27-ANODE)") (class "Default")
      (node (ref "D27") (pin "A") (pinfunction "ANODE_A") (pintype "passive"))
      (node (ref "JP59") (pin "2") (pinfunction "2_2") (pintype "passive"))
      (node (ref "JP60") (pin "2") (pinfunction "2_2") (pintype "passive"))
    )
    (net (code "44") (name "Net-(D27-CATHODE)") (class "Default")
      (node (ref "D27") (pin "K") (pinfunction "CATHODE_K") (pintype "passive"))
      (node (ref "JP59") (pin "1") (pinfunction "1_1") (pintype "passive"))
      (node (ref "JP71") (pin "2") (pinfunction "2_2") (pintype "passive"))
    )
    (net (code "45") (name "Net-(D28-ANODE)") (class "Default")
      (node (ref "D28") (pin "A") (pinfunction "ANODE_A") (pintype "passive"))
      (node (ref "JP61") (pin "2") (pinfunction "2_2") (pintype "passive"))
      (node (ref "JP62") (pin "2") (pinfunction "2_2") (pintype "passive"))
    )
    (net (code "46") (name "Net-(D28-CATHODE)") (class "Default")
      (node (ref "D28") (pin "K") (pinfunction "CATHODE_K") (pintype "passive"))
      (node (ref "JP61") (pin "1") (pinfunction "1_1") (pintype "passive"))
      (node (ref "JP72") (pin "2") (pinfunction "2_2") (pintype "passive"))
    )
    (net (code "47") (name "Net-(JP18-Pad2)") (class "Default")
      (node (ref "JP18") (pin "2") (pinfunction "2_2") (pintype "passive"))
      (node (ref "R43") (pin "2") (pinfunction "2_2") (pintype "passive"))
    )
    (net (code "48") (name "Net-(JP21-Pad2)") (class "Default")
      (node (ref "JP21") (pin "2") (pinfunction "2_2") (pintype "passive"))
      (node (ref "R46") (pin "2") (pinfunction "2_2") (pintype "passive"))
    )
    (net (code "49") (name "Net-(JP24-Pad2)") (class "Default")
      (node (ref "JP24") (pin "2") (pinfunction "2_2") (pintype "passive"))
      (node (ref "R49") (pin "2") (pinfunction "2_2") (pintype "passive"))
    )
    (net (code "50") (name "Net-(JP30-Pad2)") (class "Default")
      (node (ref "JP30") (pin "2") (pinfunction "2_2") (pintype "passive"))
      (node (ref "R51") (pin "2") (pinfunction "2_2") (pintype "passive"))
    )
    (net (code "51") (name "Net-(JP33-Pad2)") (class "Default")
      (node (ref "JP33") (pin "2") (pinfunction "2_2") (pintype "passive"))
      (node (ref "R54") (pin "2") (pinfunction "2_2") (pintype "passive"))
    )
    (net (code "52") (name "Net-(JP36-Pad2)") (class "Default")
      (node (ref "JP36") (pin "2") (pinfunction "2_2") (pintype "passive"))
      (node (ref "R57") (pin "2") (pinfunction "2_2") (pintype "passive"))
    )
    (net (code "53") (name "Net-(JP38-Pad2)") (class "Default")
      (node (ref "JP38") (pin "2") (pinfunction "2_2") (pintype "passive"))
      (node (ref "R62") (pin "2") (pinfunction "2_2") (pintype "passive"))
    )
    (net (code "54") (name "Net-(JP40-Pad2)") (class "Default")
      (node (ref "JP40") (pin "2") (pinfunction "2_2") (pintype "passive"))
      (node (ref "R74") (pin "2") (pinfunction "2_2") (pintype "passive"))
    )
    (net (code "55") (name "Net-(JP42-Pad2)") (class "Default")
      (node (ref "JP42") (pin "2") (pinfunction "2_2") (pintype "passive"))
      (node (ref "R75") (pin "2") (pinfunction "2_2") (pintype "passive"))
    )
    (net (code "56") (name "Net-(JP44-Pad2)") (class "Default")
      (node (ref "JP44") (pin "2") (pinfunction "2_2") (pintype "passive"))
      (node (ref "R76") (pin "2") (pinfunction "2_2") (pintype "passive"))
    )
    (net (code "57") (name "Net-(JP46-Pad2)") (class "Default")
      (node (ref "JP46") (pin "2") (pinfunction "2_2") (pintype "passive"))
      (node (ref "R77") (pin "2") (pinfunction "2_2") (pintype "passive"))
    )
    (net (code "58") (name "Net-(JP48-Pad2)") (class "Default")
      (node (ref "JP48") (pin "2") (pinfunction "2_2") (pintype "passive"))
      (node (ref "R78") (pin "2") (pinfunction "2_2") (pintype "passive"))
    )
    (net (code "59") (name "Net-(Q1-D)") (class "Default")
      (node (ref "JP1") (pin "1") (pinfunction "1_1") (pintype "passive"))
      (node (ref "Q1") (pin "3") (pinfunction "D_3") (pintype "bidirectional"))
    )
    (net (code "60") (name "Net-(Q1-G)") (class "Default")
      (node (ref "JP3") (pin "3") (pinfunction "3_3") (pintype "passive"))
      (node (ref "Q1") (pin "1") (pinfunction "G_1") (pintype "bidirectional"))
      (node (ref "Q2") (pin "3") (pinfunction "D_3") (pintype "bidirectional"))
      (node (ref "R5") (pin "2") (pinfunction "2_2") (pintype "passive"))
    )
    (net (code "61") (name "Net-(Q3-G)") (class "Default")
      (node (ref "Q3") (pin "4") (pinfunction "G_4") (pintype "bidirectional"))
      (node (ref "Q4") (pin "3") (pinfunction "D_3") (pintype "bidirectional"))
      (node (ref "R6") (pin "1") (pinfunction "1_1") (pintype "passive"))
    )
    (net (code "62") (name "Net-(Q3-S-Pad1)") (class "Default")
      (node (ref "Q3") (pin "1") (pinfunction "S_1") (pintype "bidirectional"))
      (node (ref "Q3") (pin "2") (pinfunction "S_2") (pintype "bidirectional"))
      (node (ref "Q3") (pin "3") (pinfunction "S_3") (pintype "bidirectional"))
      (node (ref "R10") (pin "2") (pinfunction "2_2") (pintype "passive"))
      (node (ref "R6") (pin "2") (pinfunction "2_2") (pintype "passive"))
      (node (ref "R7") (pin "1") (pinfunction "1_1") (pintype "passive"))
      (node (ref "R8") (pin "1") (pinfunction "1_1") (pintype "passive"))
    )
    (net (code "63") (name "Net-(Q5-D)") (class "Default")
      (node (ref "JP4") (pin "1") (pinfunction "1_1") (pintype "passive"))
      (node (ref "Q5") (pin "3") (pinfunction "D_3") (pintype "bidirectional"))
    )
    (net (code "64") (name "Net-(Q5-G)") (class "Default")
      (node (ref "JP6") (pin "3") (pinfunction "3_3") (pintype "passive"))
      (node (ref "Q5") (pin "1") (pinfunction "G_1") (pintype "bidirectional"))
      (node (ref "Q6") (pin "3") (pinfunction "D_3") (pintype "bidirectional"))
      (node (ref "R15") (pin "2") (pinfunction "2_2") (pintype "passive"))
    )
    (net (code "65") (name "Net-(Q7-D)") (class "Default")
      (node (ref "JP7") (pin "1") (pinfunction "1_1") (pintype "passive"))
      (node (ref "Q7") (pin "3") (pinfunction "D_3") (pintype "bidirectional"))
    )
    (net (code "66") (name "Net-(Q7-G)") (class "Default")
      (node (ref "JP9") (pin "3") (pinfunction "3_3") (pintype "passive"))
      (node (ref "Q7") (pin "1") (pinfunction "G_1") (pintype "bidirectional"))
      (node (ref "Q8") (pin "3") (pinfunction "D_3") (pintype "bidirectional"))
      (node (ref "R19") (pin "2") (pinfunction "2_2") (pintype "passive"))
    )
    (net (code "67") (name "Net-(Q9-S-Pad1)") (class "Default")
      (node (ref "Q9") (pin "1") (pinfunction "S_1") (pintype "bidirectional"))
      (node (ref "Q9") (pin "2") (pinfunction "S_2") (pintype "bidirectional"))
      (node (ref "Q9") (pin "3") (pinfunction "S_3") (pintype "bidirectional"))
      (node (ref "R24") (pin "2") (pinfunction "2_2") (pintype "passive"))
      (node (ref "R26") (pin "1") (pinfunction "1_1") (pintype "passive"))
      (node (ref "R27") (pin "1") (pinfunction "1_1") (pintype "passive"))
      (node (ref "R28") (pin "2") (pinfunction "2_2") (pintype "passive"))
    )
    (net (code "68") (name "Net-(Q10-D)") (class "Default")
      (node (ref "Q10") (pin "3") (pinfunction "D_3") (pintype "bidirectional"))
      (node (ref "Q9") (pin "4") (pinfunction "G_4") (pintype "bidirectional"))
      (node (ref "R24") (pin "1") (pinfunction "1_1") (pintype "passive"))
    )
    (net (code "69") (name "Net-(Q11-D)") (class "Default")
      (node (ref "JP10") (pin "1") (pinfunction "1_1") (pintype "passive"))
      (node (ref "Q11") (pin "3") (pinfunction "D_3") (pintype "bidirectional"))
    )
    (net (code "70") (name "Net-(Q11-G)") (class "Default")
      (node (ref "JP12") (pin "3") (pinfunction "3_3") (pintype "passive"))
      (node (ref "Q11") (pin "1") (pinfunction "G_1") (pintype "bidirectional"))
      (node (ref "Q12") (pin "3") (pinfunction "D_3") (pintype "bidirectional"))
      (node (ref "R25") (pin "2") (pinfunction "2_2") (pintype "passive"))
    )
    (net (code "71") (name "Net-(Q13-D)") (class "Default")
      (node (ref "JP13") (pin "1") (pinfunction "1_1") (pintype "passive"))
      (node (ref "Q13") (pin "3") (pinfunction "D_3") (pintype "bidirectional"))
    )
    (net (code "72") (name "Net-(Q13-G)") (class "Default")
      (node (ref "JP15") (pin "3") (pinfunction "3_3") (pintype "passive"))
      (node (ref "Q13") (pin "1") (pinfunction "G_1") (pintype "bidirectional"))
      (node (ref "Q14") (pin "3") (pinfunction "D_3") (pintype "bidirectional"))
      (node (ref "R38") (pin "2") (pinfunction "2_2") (pintype "passive"))
    )
    (net (code "73") (name "Net-(Q15-D)") (class "Default")
      (node (ref "JP16") (pin "2") (pinfunction "2_2") (pintype "passive"))
      (node (ref "Q15") (pin "3") (pinfunction "D_3") (pintype "bidirectional"))
      (node (ref "R43") (pin "1") (pinfunction "1_1") (pintype "passive"))
    )
    (net (code "74") (name "Net-(Q16-D)") (class "Default")
      (node (ref "JP17") (pin "1") (pinfunction "1_1") (pintype "passive"))
      (node (ref "Q16") (pin "3") (pinfunction "D_3") (pintype "bidirectional"))
    )
    (net (code "75") (name "Net-(Q16-G)") (class "Default")
      (node (ref "JP22") (pin "3") (pinfunction "3_3") (pintype "passive"))
      (node (ref "Q16") (pin "1") (pinfunction "G_1") (pintype "bidirectional"))
      (node (ref "Q18") (pin "3") (pinfunction "D_3") (pintype "bidirectional"))
      (node (ref "R47") (pin "2") (pinfunction "2_2") (pintype "passive"))
    )
    (net (code "76") (name "Net-(Q17-D)") (class "Default")
      (node (ref "JP20") (pin "2") (pinfunction "2_2") (pintype "passive"))
      (node (ref "Q17") (pin "3") (pinfunction "D_3") (pintype "bidirectional"))
      (node (ref "R46") (pin "1") (pinfunction "1_1") (pintype "passive"))
    )
    (net (code "77") (name "Net-(Q19-D)") (class "Default")
      (node (ref "JP23") (pin "2") (pinfunction "2_2") (pintype "passive"))
      (node (ref "Q19") (pin "3") (pinfunction "D_3") (pintype "bidirectional"))
      (node (ref "R49") (pin "1") (pinfunction "1_1") (pintype "passive"))
    )
    (net (code "78") (name "Net-(Q20-D)") (class "Default")
      (node (ref "JP27") (pin "2") (pinfunction "2_2") (pintype "passive"))
      (node (ref "Q20") (pin "3") (pinfunction "D_3") (pintype "bidirectional"))
      (node (ref "R51") (pin "1") (pinfunction "1_1") (pintype "passive"))
    )
    (net (code "79") (name "Net-(Q21-D)") (class "Default")
      (node (ref "JP29") (pin "1") (pinfunction "1_1") (pintype "passive"))
      (node (ref "Q21") (pin "3") (pinfunction "D_3") (pintype "bidirectional"))
    )
    (net (code "80") (name "Net-(Q21-G)") (class "Default")
      (node (ref "JP34") (pin "3") (pinfunction "3_3") (pintype "passive"))
      (node (ref "Q21") (pin "1") (pinfunction "G_1") (pintype "bidirectional"))
      (node (ref "Q23") (pin "3") (pinfunction "D_3") (pintype "bidirectional"))
      (node (ref "R55") (pin "2") (pinfunction "2_2") (pintype "passive"))
    )
    (net (code "81") (name "Net-(Q22-D)") (class "Default")
      (node (ref "JP32") (pin "2") (pinfunction "2_2") (pintype "passive"))
      (node (ref "Q22") (pin "3") (pinfunction "D_3") (pintype "bidirectional"))
      (node (ref "R54") (pin "1") (pinfunction "1_1") (pintype "passive"))
    )
    (net (code "82") (name "Net-(Q24-D)") (class "Default")
      (node (ref "JP35") (pin "2") (pinfunction "2_2") (pintype "passive"))
      (node (ref "Q24") (pin "3") (pinfunction "D_3") (pintype "bidirectional"))
      (node (ref "R57") (pin "1") (pinfunction "1_1") (pintype "passive"))
    )
    (net (code "83") (name "Net-(Q25-D)") (class "Default")
      (node (ref "JP37") (pin "2") (pinfunction "2_2") (pintype "passive"))
      (node (ref "Q25") (pin "3") (pinfunction "D_3") (pintype "bidirectional"))
      (node (ref "R62") (pin "1") (pinfunction "1_1") (pintype "passive"))
    )
    (net (code "84") (name "Net-(Q26-G)") (class "Default")
      (node (ref "Q26") (pin "4") (pinfunction "G_4") (pintype "bidirectional"))
      (node (ref "Q27") (pin "3") (pinfunction "D_3") (pintype "bidirectional"))
      (node (ref "R63") (pin "1") (pinfunction "1_1") (pintype "passive"))
    )
    (net (code "85") (name "Net-(Q26-S-Pad1)") (class "Default")
      (node (ref "Q26") (pin "1") (pinfunction "S_1") (pintype "bidirectional"))
      (node (ref "Q26") (pin "2") (pinfunction "S_2") (pintype "bidirectional"))
      (node (ref "Q26") (pin "3") (pinfunction "S_3") (pintype "bidirectional"))
      (node (ref "R61") (pin "1") (pinfunction "1_1") (pintype "passive"))
      (node (ref "R63") (pin "2") (pinfunction "2_2") (pintype "passive"))
      (node (ref "R71") (pin "2") (pinfunction "2_2") (pintype "passive"))
      (node (ref "R73") (pin "1") (pinfunction "1_1") (pintype "passive"))
    )
    (net (code "86") (name "Net-(Q28-D)") (class "Default")
      (node (ref "JP39") (pin "2") (pinfunction "2_2") (pintype "passive"))
      (node (ref "Q28") (pin "3") (pinfunction "D_3") (pintype "bidirectional"))
      (node (ref "R74") (pin "1") (pinfunction "1_1") (pintype "passive"))
    )
    (net (code "87") (name "Net-(Q29-D)") (class "Default")
      (node (ref "JP41") (pin "2") (pinfunction "2_2") (pintype "passive"))
      (node (ref "Q29") (pin "3") (pinfunction "D_3") (pintype "bidirectional"))
      (node (ref "R75") (pin "1") (pinfunction "1_1") (pintype "passive"))
    )
    (net (code "88") (name "Net-(Q30-D)") (class "Default")
      (node (ref "JP43") (pin "2") (pinfunction "2_2") (pintype "passive"))
      (node (ref "Q30") (pin "3") (pinfunction "D_3") (pintype "bidirectional"))
      (node (ref "R76") (pin "1") (pinfunction "1_1") (pintype "passive"))
    )
    (net (code "89") (name "Net-(Q31-D)") (class "Default")
      (node (ref "JP45") (pin "2") (pinfunction "2_2") (pintype "passive"))
      (node (ref "Q31") (pin "3") (pinfunction "D_3") (pintype "bidirectional"))
      (node (ref "R77") (pin "1") (pinfunction "1_1") (pintype "passive"))
    )
    (net (code "90") (name "Net-(Q32-D)") (class "Default")
      (node (ref "JP47") (pin "2") (pinfunction "2_2") (pintype "passive"))
      (node (ref "Q32") (pin "3") (pinfunction "D_3") (pintype "bidirectional"))
      (node (ref "R78") (pin "1") (pinfunction "1_1") (pintype "passive"))
    )
    (net (code "91") (name "Net-(Q33-D)") (class "Default")
      (node (ref "JP66") (pin "1") (pinfunction "1_1") (pintype "passive"))
      (node (ref "Q33") (pin "3") (pinfunction "D_3") (pintype "bidirectional"))
    )
    (net (code "92") (name "Net-(Q33-G)") (class "Default")
      (node (ref "JP50") (pin "3") (pinfunction "3_3") (pintype "passive"))
      (node (ref "Q33") (pin "1") (pinfunction "G_1") (pintype "bidirectional"))
      (node (ref "Q36") (pin "3") (pinfunction "D_3") (pintype "bidirectional"))
      (node (ref "R98") (pin "2") (pinfunction "2_2") (pintype "passive"))
    )
    (net (code "93") (name "Net-(Q34-G)") (class "Default")
      (node (ref "Q34") (pin "4") (pinfunction "G_4") (pintype "bidirectional"))
      (node (ref "Q35") (pin "3") (pinfunction "D_3") (pintype "bidirectional"))
      (node (ref "R87") (pin "1") (pinfunction "1_1") (pintype "passive"))
    )
    (net (code "94") (name "Net-(Q34-S-Pad1)") (class "Default")
      (node (ref "Q34") (pin "1") (pinfunction "S_1") (pintype "bidirectional"))
      (node (ref "Q34") (pin "2") (pinfunction "S_2") (pintype "bidirectional"))
      (node (ref "Q34") (pin "3") (pinfunction "S_3") (pintype "bidirectional"))
      (node (ref "R86") (pin "1") (pinfunction "1_1") (pintype "passive"))
      (node (ref "R87") (pin "2") (pinfunction "2_2") (pintype "passive"))
      (node (ref "R92") (pin "2") (pinfunction "2_2") (pintype "passive"))
      (node (ref "R94") (pin "1") (pinfunction "1_1") (pintype "passive"))
    )
    (net (code "95") (name "Net-(Q37-D)") (class "Default")
      (node (ref "JP67") (pin "1") (pinfunction "1_1") (pintype "passive"))
      (node (ref "Q37") (pin "3") (pinfunction "D_3") (pintype "bidirectional"))
    )
    (net (code "96") (name "Net-(Q37-G)") (class "Default")
      (node (ref "JP52") (pin "3") (pinfunction "3_3") (pintype "passive"))
      (node (ref "Q37") (pin "1") (pinfunction "G_1") (pintype "bidirectional"))
      (node (ref "Q38") (pin "3") (pinfunction "D_3") (pintype "bidirectional"))
      (node (ref "R100") (pin "2") (pinfunction "2_2") (pintype "passive"))
    )
    (net (code "97") (name "Net-(Q39-D)") (class "Default")
      (node (ref "JP68") (pin "1") (pinfunction "1_1") (pintype "passive"))
      (node (ref "Q39") (pin "3") (pinfunction "D_3") (pintype "bidirectional"))
    )
    (net (code "98") (name "Net-(Q39-G)") (class "Default")
      (node (ref "JP54") (pin "3") (pinfunction "3_3") (pintype "passive"))
      (node (ref "Q39") (pin "1") (pinfunction "G_1") (pintype "bidirectional"))
      (node (ref "Q40") (pin "3") (pinfunction "D_3") (pintype "bidirectional"))
      (node (ref "R102") (pin "2") (pinfunction "2_2") (pintype "passive"))
    )
    (net (code "99") (name "Net-(Q41-D)") (class "Default")
      (node (ref "JP69") (pin "1") (pinfunction "1_1") (pintype "passive"))
      (node (ref "Q41") (pin "3") (pinfunction "D_3") (pintype "bidirectional"))
    )
    (net (code "100") (name "Net-(Q41-G)") (class "Default")
      (node (ref "JP56") (pin "3") (pinfunction "3_3") (pintype "passive"))
      (node (ref "Q41") (pin "1") (pinfunction "G_1") (pintype "bidirectional"))
      (node (ref "Q42") (pin "3") (pinfunction "D_3") (pintype "bidirectional"))
      (node (ref "R104") (pin "2") (pinfunction "2_2") (pintype "passive"))
    )
    (net (code "101") (name "Net-(Q43-D)") (class "Default")
      (node (ref "JP70") (pin "1") (pinfunction "1_1") (pintype "passive"))
      (node (ref "Q43") (pin "3") (pinfunction "D_3") (pintype "bidirectional"))
    )
    (net (code "102") (name "Net-(Q43-G)") (class "Default")
      (node (ref "JP58") (pin "3") (pinfunction "3_3") (pintype "passive"))
      (node (ref "Q43") (pin "1") (pinfunction "G_1") (pintype "bidirectional"))
      (node (ref "Q44") (pin "3") (pinfunction "D_3") (pintype "bidirectional"))
      (node (ref "R106") (pin "2") (pinfunction "2_2") (pintype "passive"))
    )
    (net (code "103") (name "Net-(Q45-D)") (class "Default")
      (node (ref "JP71") (pin "1") (pinfunction "1_1") (pintype "passive"))
      (node (ref "Q45") (pin "3") (pinfunction "D_3") (pintype "bidirectional"))
    )
    (net (code "104") (name "Net-(Q45-G)") (class "Default")
      (node (ref "JP60") (pin "3") (pinfunction "3_3") (pintype "passive"))
      (node (ref "Q45") (pin "1") (pinfunction "G_1") (pintype "bidirectional"))
      (node (ref "Q46") (pin "3") (pinfunction "D_3") (pintype "bidirectional"))
      (node (ref "R108") (pin "2") (pinfunction "2_2") (pintype "passive"))
    )
    (net (code "105") (name "Net-(Q47-D)") (class "Default")
      (node (ref "JP72") (pin "1") (pinfunction "1_1") (pintype "passive"))
      (node (ref "Q47") (pin "3") (pinfunction "D_3") (pintype "bidirectional"))
    )
    (net (code "106") (name "Net-(Q47-G)") (class "Default")
      (node (ref "JP62") (pin "3") (pinfunction "3_3") (pintype "passive"))
      (node (ref "Q47") (pin "1") (pinfunction "G_1") (pintype "bidirectional"))
      (node (ref "Q48") (pin "3") (pinfunction "D_3") (pintype "bidirectional"))
      (node (ref "R110") (pin "2") (pinfunction "2_2") (pintype "passive"))
    )
    (net (code "107") (name "Net-(U1A-VIN+)") (class "Default")
      (node (ref "R11") (pin "1") (pinfunction "1_1") (pintype "passive"))
      (node (ref "R13") (pin "1") (pinfunction "1_1") (pintype "passive"))
      (node (ref "U1") (pin "3") (pinfunction "VIN+_3") (pintype "bidirectional"))
    )
    (net (code "108") (name "Net-(U1A-VIN-)") (class "Default")
      (node (ref "R10") (pin "1") (pinfunction "1_1") (pintype "passive"))
      (node (ref "R14") (pin "1") (pinfunction "1_1") (pintype "passive"))
      (node (ref "U1") (pin "2") (pinfunction "VIN-_2") (pintype "bidirectional"))
    )
    (net (code "109") (name "Net-(U1A-VOUT)") (class "Default")
      (node (ref "R14") (pin "2") (pinfunction "2_2") (pintype "passive"))
      (node (ref "R16") (pin "1") (pinfunction "1_1") (pintype "passive"))
      (node (ref "U1") (pin "1") (pinfunction "VOUT_1") (pintype "bidirectional"))
    )
    (net (code "110") (name "Net-(U1B-VIN+)") (class "Default")
      (node (ref "R29") (pin "1") (pinfunction "1_1") (pintype "passive"))
      (node (ref "R32") (pin "1") (pinfunction "1_1") (pintype "passive"))
      (node (ref "U1") (pin "5") (pinfunction "VIN+_5") (pintype "bidirectional"))
    )
    (net (code "111") (name "Net-(U1B-VIN-)") (class "Default")
      (node (ref "R28") (pin "1") (pinfunction "1_1") (pintype "passive"))
      (node (ref "R34") (pin "1") (pinfunction "1_1") (pintype "passive"))
      (node (ref "U1") (pin "6") (pinfunction "VIN-_6") (pintype "bidirectional"))
    )
    (net (code "112") (name "Net-(U1B-VOUT)") (class "Default")
      (node (ref "R34") (pin "2") (pinfunction "2_2") (pintype "passive"))
      (node (ref "R37") (pin "1") (pinfunction "1_1") (pintype "passive"))
      (node (ref "U1") (pin "7") (pinfunction "VOUT_7") (pintype "bidirectional"))
    )
    (net (code "113") (name "Net-(U4-FB)") (class "Default")
      (node (ref "R39") (pin "1") (pinfunction "1_1") (pintype "passive"))
      (node (ref "R40") (pin "2") (pinfunction "2_2") (pintype "passive"))
      (node (ref "U4") (pin "3") (pinfunction "FB_3") (pintype "bidirectional"))
    )
    (net (code "114") (name "Net-(U4-OC)") (class "Default")
      (node (ref "R35") (pin "2") (pinfunction "2_2") (pintype "passive"))
      (node (ref "U4") (pin "6") (pinfunction "OC_6") (pintype "bidirectional"))
    )
    (net (code "115") (name "Net-(U5-A12{slash}D+)") (class "Default")
      (node (ref "R42") (pin "2") (pinfunction "2_2") (pintype "passive"))
      (node (ref "U5") (pin "A12") (pinfunction "A12/D+_A12") (pintype "bidirectional"))
    )
    (net (code "116") (name "Net-(U7-A12{slash}D+)") (class "Default")
      (node (ref "R60") (pin "2") (pinfunction "2_2") (pintype "passive"))
      (node (ref "U7") (pin "A12") (pinfunction "A12/D+_A12") (pintype "bidirectional"))
    )
    (net (code "117") (name "Net-(U9-FB)") (class "Default")
      (node (ref "R66") (pin "1") (pinfunction "1_1") (pintype "passive"))
      (node (ref "R67") (pin "2") (pinfunction "2_2") (pintype "passive"))
      (node (ref "U9") (pin "3") (pinfunction "FB_3") (pintype "bidirectional"))
    )
    (net (code "118") (name "Net-(U9-OC)") (class "Default")
      (node (ref "R68") (pin "2") (pinfunction "2_2") (pintype "passive"))
      (node (ref "U9") (pin "6") (pinfunction "OC_6") (pintype "bidirectional"))
    )
    (net (code "119") (name "Net-(U10A-VIN+)") (class "Default")
      (node (ref "R69") (pin "1") (pinfunction "1_1") (pintype "passive"))
      (node (ref "R70") (pin "1") (pinfunction "1_1") (pintype "passive"))
      (node (ref "U10") (pin "3") (pinfunction "VIN+_3") (pintype "bidirectional"))
    )
    (net (code "120") (name "Net-(U10A-VIN-)") (class "Default")
      (node (ref "R71") (pin "1") (pinfunction "1_1") (pintype "passive"))
      (node (ref "R72") (pin "1") (pinfunction "1_1") (pintype "passive"))
      (node (ref "U10") (pin "2") (pinfunction "VIN-_2") (pintype "bidirectional"))
    )
    (net (code "121") (name "Net-(U10A-VOUT)") (class "Default")
      (node (ref "R72") (pin "2") (pinfunction "2_2") (pintype "passive"))
      (node (ref "R95") (pin "1") (pinfunction "1_1") (pintype "passive"))
      (node (ref "U10") (pin "1") (pinfunction "VOUT_1") (pintype "bidirectional"))
    )
    (net (code "122") (name "Net-(U10B-VIN+)") (class "Default")
      (node (ref "R90") (pin "1") (pinfunction "1_1") (pintype "passive"))
      (node (ref "R91") (pin "1") (pinfunction "1_1") (pintype "passive"))
      (node (ref "U10") (pin "5") (pinfunction "VIN+_5") (pintype "bidirectional"))
    )
    (net (code "123") (name "Net-(U10B-VIN-)") (class "Default")
      (node (ref "R92") (pin "1") (pinfunction "1_1") (pintype "passive"))
      (node (ref "R93") (pin "1") (pinfunction "1_1") (pintype "passive"))
      (node (ref "U10") (pin "6") (pinfunction "VIN-_6") (pintype "bidirectional"))
    )
    (net (code "124") (name "Net-(U10B-VOUT)") (class "Default")
      (node (ref "R93") (pin "2") (pinfunction "2_2") (pintype "passive"))
      (node (ref "R96") (pin "1") (pinfunction "1_1") (pintype "passive"))
      (node (ref "U10") (pin "7") (pinfunction "VOUT_7") (pintype "bidirectional"))
    )
    (net (code "125") (name "OD_1") (class "Default")
      (node (ref "Q24") (pin "1") (pinfunction "G_1") (pintype "bidirectional"))
      (node (ref "Q32") (pin "1") (pinfunction "G_1") (pintype "bidirectional"))
      (node (ref "R56") (pin "2") (pinfunction "2_2") (pintype "passive"))
      (node (ref "R84") (pin "2") (pinfunction "2_2") (pintype "passive"))
      (node (ref "U5") (pin "B12") (pinfunction "B12_B12") (pintype "bidirectional"))
      (node (ref "U7") (pin "B12") (pinfunction "B12_B12") (pintype "bidirectional"))
    )
    (net (code "126") (name "OD_2") (class "Default")
      (node (ref "Q22") (pin "1") (pinfunction "G_1") (pintype "bidirectional"))
      (node (ref "Q31") (pin "1") (pinfunction "G_1") (pintype "bidirectional"))
      (node (ref "R52") (pin "2") (pinfunction "2_2") (pintype "passive"))
      (node (ref "R83") (pin "2") (pinfunction "2_2") (pintype "passive"))
      (node (ref "U5") (pin "B14") (pinfunction "B14_B14") (pintype "bidirectional"))
      (node (ref "U7") (pin "B14") (pinfunction "B14_B14") (pintype "bidirectional"))
    )
    (net (code "127") (name "OD_3") (class "Default")
      (node (ref "Q20") (pin "1") (pinfunction "G_1") (pintype "bidirectional"))
      (node (ref "Q30") (pin "1") (pinfunction "G_1") (pintype "bidirectional"))
      (node (ref "R50") (pin "2") (pinfunction "2_2") (pintype "passive"))
      (node (ref "R82") (pin "2") (pinfunction "2_2") (pintype "passive"))
      (node (ref "U5") (pin "A8") (pinfunction "A8_A8") (pintype "bidirectional"))
      (node (ref "U7") (pin "A8") (pinfunction "A8_A8") (pintype "bidirectional"))
    )
    (net (code "128") (name "OD_4") (class "Default")
      (node (ref "Q19") (pin "1") (pinfunction "G_1") (pintype "bidirectional"))
      (node (ref "Q29") (pin "1") (pinfunction "G_1") (pintype "bidirectional"))
      (node (ref "R48") (pin "2") (pinfunction "2_2") (pintype "passive"))
      (node (ref "R81") (pin "2") (pinfunction "2_2") (pintype "passive"))
      (node (ref "U5") (pin "A10") (pinfunction "A10_A10") (pintype "bidirectional"))
      (node (ref "U7") (pin "A10") (pinfunction "A10_A10") (pintype "bidirectional"))
    )
    (net (code "129") (name "OD_5") (class "Default")
      (node (ref "Q17") (pin "1") (pinfunction "G_1") (pintype "bidirectional"))
      (node (ref "Q28") (pin "1") (pinfunction "G_1") (pintype "bidirectional"))
      (node (ref "R44") (pin "2") (pinfunction "2_2") (pintype "passive"))
      (node (ref "R80") (pin "2") (pinfunction "2_2") (pintype "passive"))
      (node (ref "U5") (pin "B3") (pinfunction "B3_B3") (pintype "bidirectional"))
      (node (ref "U7") (pin "B3") (pinfunction "B3_B3") (pintype "bidirectional"))
    )
    (net (code "130") (name "OD_6") (class "Default")
      (node (ref "Q15") (pin "1") (pinfunction "G_1") (pintype "bidirectional"))
      (node (ref "Q25") (pin "1") (pinfunction "G_1") (pintype "bidirectional"))
      (node (ref "R41") (pin "2") (pinfunction "2_2") (pintype "passive"))
      (node (ref "R79") (pin "2") (pinfunction "2_2") (pintype "passive"))
      (node (ref "U5") (pin "B5") (pinfunction "B5_B5") (pintype "bidirectional"))
      (node (ref "U7") (pin "B5") (pinfunction "B5_B5") (pintype "bidirectional"))
    )
    (net (code "131") (name "RLY_1") (class "Default")
      (node (ref "Q2") (pin "1") (pinfunction "G_1") (pintype "bidirectional"))
      (node (ref "Q36") (pin "1") (pinfunction "G_1") (pintype "bidirectional"))
      (node (ref "R2") (pin "2") (pinfunction "2_2") (pintype "passive"))
      (node (ref "R97") (pin "2") (pinfunction "2_2") (pintype "passive"))
      (node (ref "U5") (pin "B13") (pinfunction "B13_B13") (pintype "bidirectional"))
      (node (ref "U7") (pin "B13") (pinfunction "B13_B13") (pintype "bidirectional"))
    )
    (net (code "132") (name "RLY_2") (class "Default")
      (node (ref "Q38") (pin "1") (pinfunction "G_1") (pintype "bidirectional"))
      (node (ref "Q6") (pin "1") (pinfunction "G_1") (pintype "bidirectional"))
      (node (ref "R12") (pin "2") (pinfunction "2_2") (pintype "passive"))
      (node (ref "R99") (pin "2") (pinfunction "2_2") (pintype "passive"))
      (node (ref "U5") (pin "B15") (pinfunction "B15_B15") (pintype "bidirectional"))
      (node (ref "U7") (pin "B15") (pinfunction "B15_B15") (pintype "bidirectional"))
    )
    (net (code "133") (name "RLY_3") (class "Default")
      (node (ref "Q40") (pin "1") (pinfunction "G_1") (pintype "bidirectional"))
      (node (ref "Q8") (pin "1") (pinfunction "G_1") (pintype "bidirectional"))
      (node (ref "R101") (pin "2") (pinfunction "2_2") (pintype "passive"))
      (node (ref "R17") (pin "2") (pinfunction "2_2") (pintype "passive"))
      (node (ref "U5") (pin "A9") (pinfunction "A9_A9") (pintype "bidirectional"))
      (node (ref "U7") (pin "A9") (pinfunction "A9_A9") (pintype "bidirectional"))
    )
    (net (code "134") (name "RLY_4") (class "Default")
      (node (ref "Q12") (pin "1") (pinfunction "G_1") (pintype "bidirectional"))
      (node (ref "Q42") (pin "1") (pinfunction "G_1") (pintype "bidirectional"))
      (node (ref "R103") (pin "2") (pinfunction "2_2") (pintype "passive"))
      (node (ref "R23") (pin "2") (pinfunction "2_2") (pintype "passive"))
      (node (ref "U5") (pin "A15") (pinfunction "A15_A15") (pintype "bidirectional"))
      (node (ref "U7") (pin "A15") (pinfunction "A15_A15") (pintype "bidirectional"))
    )
    (net (code "135") (name "RLY_5") (class "Default")
      (node (ref "Q14") (pin "1") (pinfunction "G_1") (pintype "bidirectional"))
      (node (ref "Q44") (pin "1") (pinfunction "G_1") (pintype "bidirectional"))
      (node (ref "R105") (pin "2") (pinfunction "2_2") (pintype "passive"))
      (node (ref "R36") (pin "2") (pinfunction "2_2") (pintype "passive"))
      (node (ref "U5") (pin "B4") (pinfunction "B4_B4") (pintype "bidirectional"))
      (node (ref "U7") (pin "B4") (pinfunction "B4_B4") (pintype "bidirectional"))
    )
    (net (code "136") (name "RLY_6") (class "Default")
      (node (ref "Q18") (pin "1") (pinfunction "G_1") (pintype "bidirectional"))
      (node (ref "Q46") (pin "1") (pinfunction "G_1") (pintype "bidirectional"))
      (node (ref "R107") (pin "2") (pinfunction "2_2") (pintype "passive"))
      (node (ref "R45") (pin "2") (pinfunction "2_2") (pintype "passive"))
      (node (ref "U5") (pin "B6") (pinfunction "B6_B6") (pintype "bidirectional"))
      (node (ref "U7") (pin "B6") (pinfunction "B6_B6") (pintype "bidirectional"))
    )
    (net (code "137") (name "RLY_7") (class "Default")
      (node (ref "Q23") (pin "1") (pinfunction "G_1") (pintype "bidirectional"))
      (node (ref "Q48") (pin "1") (pinfunction "G_1") (pintype "bidirectional"))
      (node (ref "R109") (pin "2") (pinfunction "2_2") (pintype "passive"))
      (node (ref "R53") (pin "2") (pinfunction "2_2") (pintype "passive"))
      (node (ref "U5") (pin "B7") (pinfunction "B7_B7") (pintype "bidirectional"))
      (node (ref "U7") (pin "B7") (pinfunction "B7_B7") (pintype "bidirectional"))
    )
    (net (code "138") (name "SSRX+") (class "Default")
      (node (ref "CON3") (pin "6-SSRX+") (pinfunction "SSRX+_6-SSRX+") (pintype "bidirectional"))
      (node (ref "CON4") (pin "6-SSRX+") (pinfunction "SSRX+_6-SSRX+") (pintype "bidirectional"))
      (node (ref "CON7") (pin "6-SSRX+") (pinfunction "SSRX+_6-SSRX+") (pintype "bidirectional"))
      (node (ref "CON8") (pin "6-SSRX+") (pinfunction "SSRX+_6-SSRX+") (pintype "bidirectional"))
    )
    (net (code "139") (name "SSRX-") (class "Default")
      (node (ref "CON3") (pin "5-SSRX-") (pinfunction "SSRX-_5-SSRX-") (pintype "bidirectional"))
      (node (ref "CON4") (pin "5-SSRX-") (pinfunction "SSRX-_5-SSRX-") (pintype "bidirectional"))
      (node (ref "CON7") (pin "5-SSRX-") (pinfunction "SSRX-_5-SSRX-") (pintype "bidirectional"))
      (node (ref "CON8") (pin "5-SSRX-") (pinfunction "SSRX-_5-SSRX-") (pintype "bidirectional"))
    )
    (net (code "140") (name "SSTX+") (class "Default")
      (node (ref "CON3") (pin "9-SSTX+") (pinfunction "SSTX+_9-SSTX+") (pintype "bidirectional"))
      (node (ref "CON4") (pin "9-SSTX+") (pinfunction "SSTX+_9-SSTX+") (pintype "bidirectional"))
      (node (ref "CON7") (pin "9-SSTX+") (pinfunction "SSTX+_9-SSTX+") (pintype "bidirectional"))
      (node (ref "CON8") (pin "9-SSTX+") (pinfunction "SSTX+_9-SSTX+") (pintype "bidirectional"))
    )
    (net (code "141") (name "SSTX-") (class "Default")
      (node (ref "CON3") (pin "8-SSTX-") (pinfunction "SSTX-_8-SSTX-") (pintype "bidirectional"))
      (node (ref "CON4") (pin "8-SSTX-") (pinfunction "SSTX-_8-SSTX-") (pintype "bidirectional"))
      (node (ref "CON7") (pin "8-SSTX-") (pinfunction "SSTX-_8-SSTX-") (pintype "bidirectional"))
      (node (ref "CON8") (pin "8-SSTX-") (pinfunction "SSTX-_8-SSTX-") (pintype "bidirectional"))
    )
    (net (code "142") (name "USB2-EN") (class "Default")
      (node (ref "Q27") (pin "1") (pinfunction "G_1") (pintype "bidirectional"))
      (node (ref "Q4") (pin "1") (pinfunction "G_1") (pintype "bidirectional"))
      (node (ref "R1") (pin "1") (pinfunction "1_1") (pintype "passive"))
      (node (ref "R111") (pin "1") (pinfunction "1_1") (pintype "passive"))
      (node (ref "U5") (pin "B11") (pinfunction "B11_B11") (pintype "bidirectional"))
      (node (ref "U7") (pin "B11") (pinfunction "B11_B11") (pintype "bidirectional"))
    )
    (net (code "143") (name "USB2-ISNS") (class "Default")
      (node (ref "C34") (pin "1") (pinfunction "1_1") (pintype "passive"))
      (node (ref "C4") (pin "1") (pinfunction "1_1") (pintype "passive"))
      (node (ref "R16") (pin "2") (pinfunction "2_2") (pintype "passive"))
      (node (ref "R95") (pin "2") (pinfunction "2_2") (pintype "passive"))
      (node (ref "U5") (pin "B1") (pinfunction "B1_B1") (pintype "bidirectional"))
      (node (ref "U7") (pin "B1") (pinfunction "B1_B1") (pintype "bidirectional"))
    )
    (net (code "144") (name "USB2-TSNS") (class "Default")
      (node (ref "C26") (pin "1") (pinfunction "1_1") (pintype "passive"))
      (node (ref "C3") (pin "1") (pinfunction "1_1") (pintype "passive"))
      (node (ref "J1") (pin "2") (pinfunction "2_2") (pintype "passive"))
      (node (ref "J3") (pin "2") (pinfunction "2_2") (pintype "passive"))
      (node (ref "R59") (pin "1") (pinfunction "1_1") (pintype "passive"))
      (node (ref "R9") (pin "1") (pinfunction "1_1") (pintype "passive"))
      (node (ref "U5") (pin "A3") (pinfunction "A3_A3") (pintype "bidirectional"))
      (node (ref "U7") (pin "A3") (pinfunction "A3_A3") (pintype "bidirectional"))
    )
    (net (code "145") (name "USB2-VCC-SW") (class "Default")
      (node (ref "CON1") (pin "1-5V") (pinfunction "VCC_1-5V") (pintype "bidirectional"))
      (node (ref "CON6") (pin "1-5V") (pinfunction "VCC_1-5V") (pintype "bidirectional"))
      (node (ref "Q26") (pin "5") (pinfunction "D_5") (pintype "bidirectional"))
      (node (ref "Q26") (pin "6") (pinfunction "D_6") (pintype "bidirectional"))
      (node (ref "Q26") (pin "7") (pinfunction "D_7") (pintype "bidirectional"))
      (node (ref "Q26") (pin "8") (pinfunction "D_8") (pintype "bidirectional"))
      (node (ref "Q3") (pin "5") (pinfunction "D_5") (pintype "bidirectional"))
      (node (ref "Q3") (pin "6") (pinfunction "D_6") (pintype "bidirectional"))
      (node (ref "Q3") (pin "7") (pinfunction "D_7") (pintype "bidirectional"))
      (node (ref "Q3") (pin "8") (pinfunction "D_8") (pintype "bidirectional"))
      (node (ref "R3") (pin "2") (pinfunction "2_2") (pintype "passive"))
      (node (ref "R64") (pin "2") (pinfunction "2_2") (pintype "passive"))
    )
    (net (code "146") (name "USB2-VSNS") (class "Default")
      (node (ref "C2") (pin "1") (pinfunction "1_1") (pintype "passive"))
      (node (ref "C36") (pin "1") (pinfunction "1_1") (pintype "passive"))
      (node (ref "R3") (pin "1") (pinfunction "1_1") (pintype "passive"))
      (node (ref "R4") (pin "2") (pinfunction "2_2") (pintype "passive"))
      (node (ref "R64") (pin "1") (pinfunction "1_1") (pintype "passive"))
      (node (ref "R65") (pin "2") (pinfunction "2_2") (pintype "passive"))
      (node (ref "U5") (pin "B0") (pinfunction "B0_B0") (pintype "bidirectional"))
      (node (ref "U7") (pin "B0") (pinfunction "B0_B0") (pintype "bidirectional"))
    )
    (net (code "147") (name "USB2VIN") (class "Default")
      (node (ref "CON2") (pin "1-VCC") (pinfunction "VCC_1-VCC") (pintype "bidirectional"))
      (node (ref "CON5") (pin "1-VCC") (pinfunction "VCC_1-VCC") (pintype "bidirectional"))
      (node (ref "D15") (pin "A") (pinfunction "ANODE_A") (pintype "passive"))
      (node (ref "D18") (pin "A") (pinfunction "ANODE_A") (pintype "passive"))
      (node (ref "D2") (pin "A") (pinfunction "ANODE_A") (pintype "passive"))
      (node (ref "D9") (pin "A") (pinfunction "ANODE_A") (pintype "passive"))
      (node (ref "R11") (pin "2") (pinfunction "2_2") (pintype "passive"))
      (node (ref "R61") (pin "2") (pinfunction "2_2") (pintype "passive"))
      (node (ref "R69") (pin "2") (pinfunction "2_2") (pintype "passive"))
      (node (ref "R7") (pin "2") (pinfunction "2_2") (pintype "passive"))
      (node (ref "R73") (pin "2") (pinfunction "2_2") (pintype "passive"))
      (node (ref "R8") (pin "2") (pinfunction "2_2") (pintype "passive"))
    )
    (net (code "148") (name "USB3-EN") (class "Default")
      (node (ref "Q10") (pin "1") (pinfunction "G_1") (pintype "bidirectional"))
      (node (ref "Q35") (pin "1") (pinfunction "G_1") (pintype "bidirectional"))
      (node (ref "R112") (pin "1") (pinfunction "1_1") (pintype "passive"))
      (node (ref "R20") (pin "1") (pinfunction "1_1") (pintype "passive"))
      (node (ref "U5") (pin "B10") (pinfunction "B10_B10") (pintype "bidirectional"))
      (node (ref "U7") (pin "B10") (pinfunction "B10_B10") (pintype "bidirectional"))
    )
    (net (code "149") (name "USB3-ISNS") (class "Default")
      (node (ref "C14") (pin "1") (pinfunction "1_1") (pintype "passive"))
      (node (ref "C35") (pin "1") (pinfunction "1_1") (pintype "passive"))
      (node (ref "R37") (pin "2") (pinfunction "2_2") (pintype "passive"))
      (node (ref "R96") (pin "2") (pinfunction "2_2") (pintype "passive"))
      (node (ref "U5") (pin "A7") (pinfunction "A7_A7") (pintype "bidirectional"))
      (node (ref "U7") (pin "A7") (pinfunction "A7_A7") (pintype "bidirectional"))
    )
    (net (code "150") (name "USB3-TSNS") (class "Default")
      (node (ref "C11") (pin "1") (pinfunction "1_1") (pintype "passive"))
      (node (ref "C33") (pin "1") (pinfunction "1_1") (pintype "passive"))
      (node (ref "J2") (pin "2") (pinfunction "2_2") (pintype "passive"))
      (node (ref "J4") (pin "2") (pinfunction "2_2") (pintype "passive"))
      (node (ref "R30") (pin "1") (pinfunction "1_1") (pintype "passive"))
      (node (ref "R85") (pin "1") (pinfunction "1_1") (pintype "passive"))
      (node (ref "U5") (pin "A2") (pinfunction "A2_A2") (pintype "bidirectional"))
      (node (ref "U7") (pin "A2") (pinfunction "A2_A2") (pintype "bidirectional"))
    )
    (net (code "151") (name "USB3-VCC-SW") (class "Default")
      (node (ref "CON3") (pin "1-VBUS") (pinfunction "VBUS_1-VBUS") (pintype "bidirectional"))
      (node (ref "CON8") (pin "1-VBUS") (pinfunction "VBUS_1-VBUS") (pintype "bidirectional"))
      (node (ref "Q34") (pin "5") (pinfunction "D_5") (pintype "bidirectional"))
      (node (ref "Q34") (pin "6") (pinfunction "D_6") (pintype "bidirectional"))
      (node (ref "Q34") (pin "7") (pinfunction "D_7") (pintype "bidirectional"))
      (node (ref "Q34") (pin "8") (pinfunction "D_8") (pintype "bidirectional"))
      (node (ref "Q9") (pin "5") (pinfunction "D_5") (pintype "bidirectional"))
      (node (ref "Q9") (pin "6") (pinfunction "D_6") (pintype "bidirectional"))
      (node (ref "Q9") (pin "7") (pinfunction "D_7") (pintype "bidirectional"))
      (node (ref "Q9") (pin "8") (pinfunction "D_8") (pintype "bidirectional"))
      (node (ref "R21") (pin "2") (pinfunction "2_2") (pintype "passive"))
      (node (ref "R88") (pin "2") (pinfunction "2_2") (pintype "passive"))
    )
    (net (code "152") (name "USB3-VSNS") (class "Default")
      (node (ref "C37") (pin "1") (pinfunction "1_1") (pintype "passive"))
      (node (ref "C6") (pin "1") (pinfunction "1_1") (pintype "passive"))
      (node (ref "R21") (pin "1") (pinfunction "1_1") (pintype "passive"))
      (node (ref "R22") (pin "2") (pinfunction "2_2") (pintype "passive"))
      (node (ref "R88") (pin "1") (pinfunction "1_1") (pintype "passive"))
      (node (ref "R89") (pin "2") (pinfunction "2_2") (pintype "passive"))
      (node (ref "U5") (pin "A6") (pinfunction "A6_A6") (pintype "bidirectional"))
      (node (ref "U7") (pin "A6") (pinfunction "A6_A6") (pintype "bidirectional"))
    )
    (net (code "153") (name "USB3VIN") (class "Default")
      (node (ref "CON4") (pin "1-VBUS") (pinfunction "VBUS_1-VBUS") (pintype "bidirectional"))
      (node (ref "CON7") (pin "1-VBUS") (pinfunction "VBUS_1-VBUS") (pintype "bidirectional"))
      (node (ref "D16") (pin "A") (pinfunction "ANODE_A") (pintype "passive"))
      (node (ref "D19") (pin "A") (pinfunction "ANODE_A") (pintype "passive"))
      (node (ref "D3") (pin "A") (pinfunction "ANODE_A") (pintype "passive"))
      (node (ref "D8") (pin "A") (pinfunction "ANODE_A") (pintype "passive"))
      (node (ref "R26") (pin "2") (pinfunction "2_2") (pintype "passive"))
      (node (ref "R27") (pin "2") (pinfunction "2_2") (pintype "passive"))
      (node (ref "R29") (pin "2") (pinfunction "2_2") (pintype "passive"))
      (node (ref "R86") (pin "2") (pinfunction "2_2") (pintype "passive"))
      (node (ref "R90") (pin "2") (pinfunction "2_2") (pintype "passive"))
      (node (ref "R94") (pin "2") (pinfunction "2_2") (pintype "passive"))
    )
    (net (code "154") (name "USBBPIN") (class "Default")
      (node (ref "C16") (pin "1") (pinfunction "1_1") (pintype "passive"))
      (node (ref "C23") (pin "1") (pinfunction "1_1") (pintype "passive"))
      (node (ref "C25") (pin "1") (pinfunction "1_1") (pintype "passive"))
      (node (ref "C5") (pin "1") (pinfunction "1_1") (pintype "passive"))
      (node (ref "D17") (pin "A") (pinfunction "ANODE_A") (pintype "passive"))
      (node (ref "D20") (pin "A") (pinfunction "ANODE_A") (pintype "passive"))
      (node (ref "D4") (pin "A") (pinfunction "ANODE_A") (pintype "passive"))
      (node (ref "D7") (pin "A") (pinfunction "ANODE_A") (pintype "passive"))
      (node (ref "JP18") (pin "1") (pinfunction "1_1") (pintype "passive"))
      (node (ref "JP21") (pin "1") (pinfunction "1_1") (pintype "passive"))
      (node (ref "JP24") (pin "1") (pinfunction "1_1") (pintype "passive"))
      (node (ref "JP28") (pin "3") (pinfunction "3_3") (pintype "passive"))
      (node (ref "JP30") (pin "1") (pinfunction "1_1") (pintype "passive"))
      (node (ref "JP33") (pin "1") (pinfunction "1_1") (pintype "passive"))
      (node (ref "JP36") (pin "1") (pinfunction "1_1") (pintype "passive"))
      (node (ref "JP38") (pin "1") (pinfunction "1_1") (pintype "passive"))
      (node (ref "JP40") (pin "1") (pinfunction "1_1") (pintype "passive"))
      (node (ref "JP42") (pin "1") (pinfunction "1_1") (pintype "passive"))
      (node (ref "JP44") (pin "1") (pinfunction "1_1") (pintype "passive"))
      (node (ref "JP46") (pin "1") (pinfunction "1_1") (pintype "passive"))
      (node (ref "JP48") (pin "1") (pinfunction "1_1") (pintype "passive"))
      (node (ref "JP65") (pin "3") (pinfunction "3_3") (pintype "passive"))
      (node (ref "R18") (pin "1") (pinfunction "1_1") (pintype "passive"))
      (node (ref "R58") (pin "1") (pinfunction "1_1") (pintype "passive"))
      (node (ref "U3") (pin "3") (pinfunction "VIN_3") (pintype "bidirectional"))
      (node (ref "U5") (pin "5V") (pinfunction "5V_5V") (pintype "bidirectional"))
      (node (ref "U7") (pin "5V") (pinfunction "5V_5V") (pintype "bidirectional"))
      (node (ref "U8") (pin "3") (pinfunction "VIN_3") (pintype "bidirectional"))
    )
    (net (code "155") (name "VUSBMAX") (class "Default")
      (node (ref "C1") (pin "1") (pinfunction "1_1") (pintype "passive"))
      (node (ref "C20") (pin "1") (pinfunction "1_1") (pintype "passive"))
      (node (ref "D15") (pin "K") (pinfunction "CATHODE_K") (pintype "passive"))
      (node (ref "D16") (pin "K") (pinfunction "CATHODE_K") (pintype "passive"))
      (node (ref "D17") (pin "K") (pinfunction "CATHODE_K") (pintype "passive"))
      (node (ref "D2") (pin "K") (pinfunction "CATHODE_K") (pintype "passive"))
      (node (ref "D3") (pin "K") (pinfunction "CATHODE_K") (pintype "passive"))
      (node (ref "D4") (pin "K") (pinfunction "CATHODE_K") (pintype "passive"))
      (node (ref "U1") (pin "8") (pinfunction "VCC_8") (pintype "power_in"))
      (node (ref "U10") (pin "8") (pinfunction "VCC_8") (pintype "power_in"))
    )
    (net (code "156") (name "unconnected-(CON2-ID-Pad4-ID)") (class "Default")
      (node (ref "CON2") (pin "4-ID") (pinfunction "ID_4-ID") (pintype "bidirectional"))
    )
    (net (code "157") (name "unconnected-(CON5-ID-Pad4-ID)") (class "Default")
      (node (ref "CON5") (pin "4-ID") (pinfunction "ID_4-ID") (pintype "bidirectional"))
    )
    (net (code "158") (name "unconnected-(U5-PadRST)") (class "Default")
      (node (ref "U5") (pin "RST") (pinfunction "RST_RST") (pintype "bidirectional"))
    )
    (net (code "159") (name "unconnected-(U5-VB-PadVBAT)") (class "Default")
      (node (ref "U5") (pin "VBAT") (pinfunction "VB_VBAT") (pintype "bidirectional"))
    )
    (net (code "160") (name "unconnected-(U7-PadRST)") (class "Default")
      (node (ref "U7") (pin "RST") (pinfunction "RST_RST") (pintype "bidirectional"))
    )
    (net (code "161") (name "unconnected-(U7-VB-PadVBAT)") (class "Default")
      (node (ref "U7") (pin "VBAT") (pinfunction "VB_VBAT") (pintype "bidirectional"))
    )
  )
)
